# firefly-ice.net
KiCad netlist of a schematic drawn in EAGLE
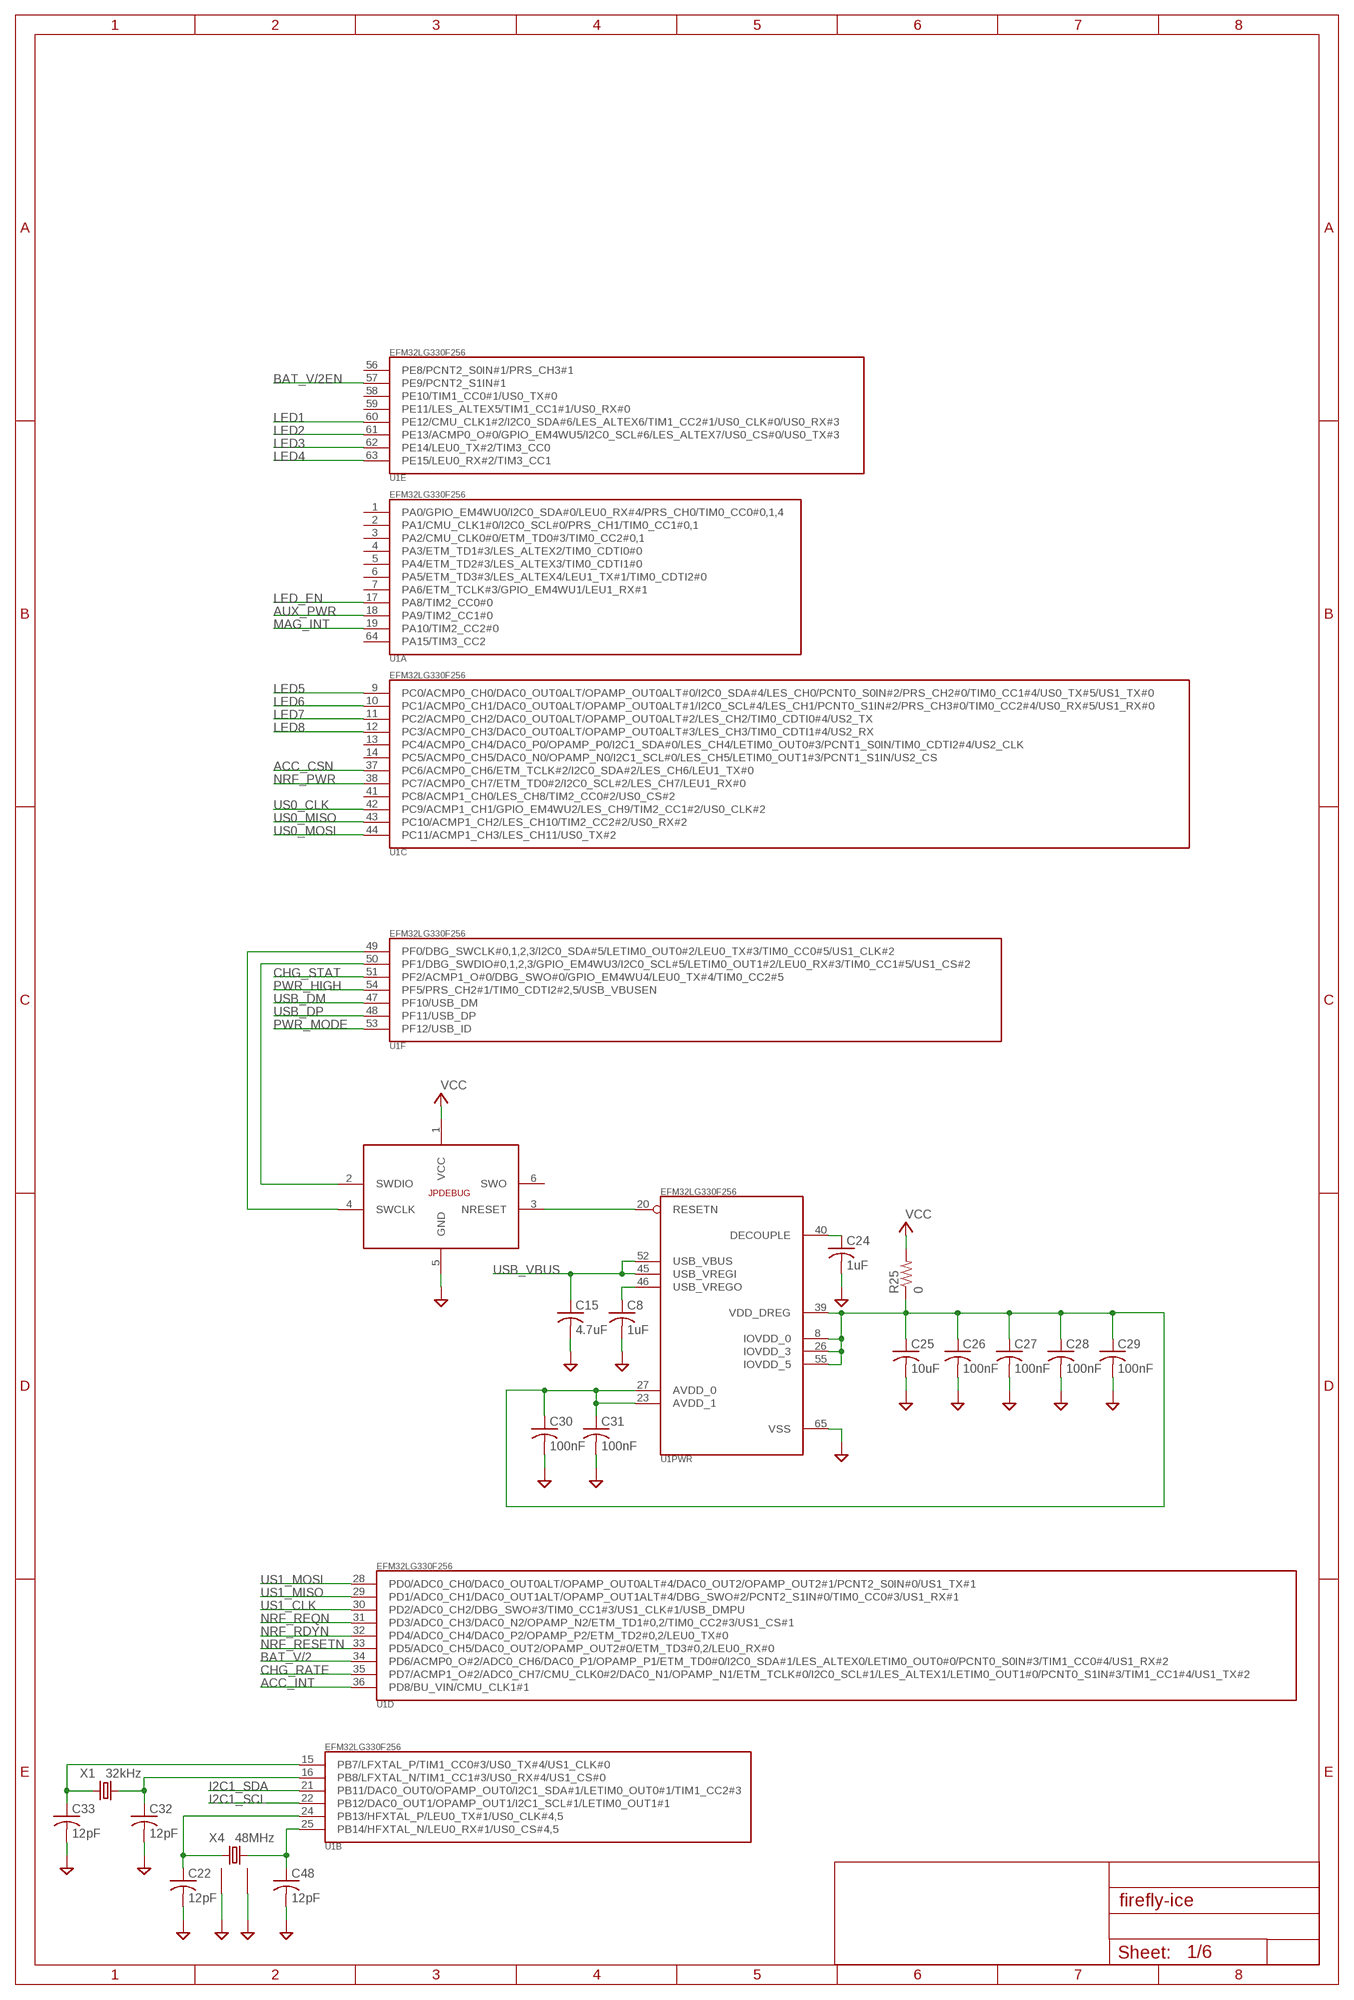
[diagram p0: schematic, sheet 1]
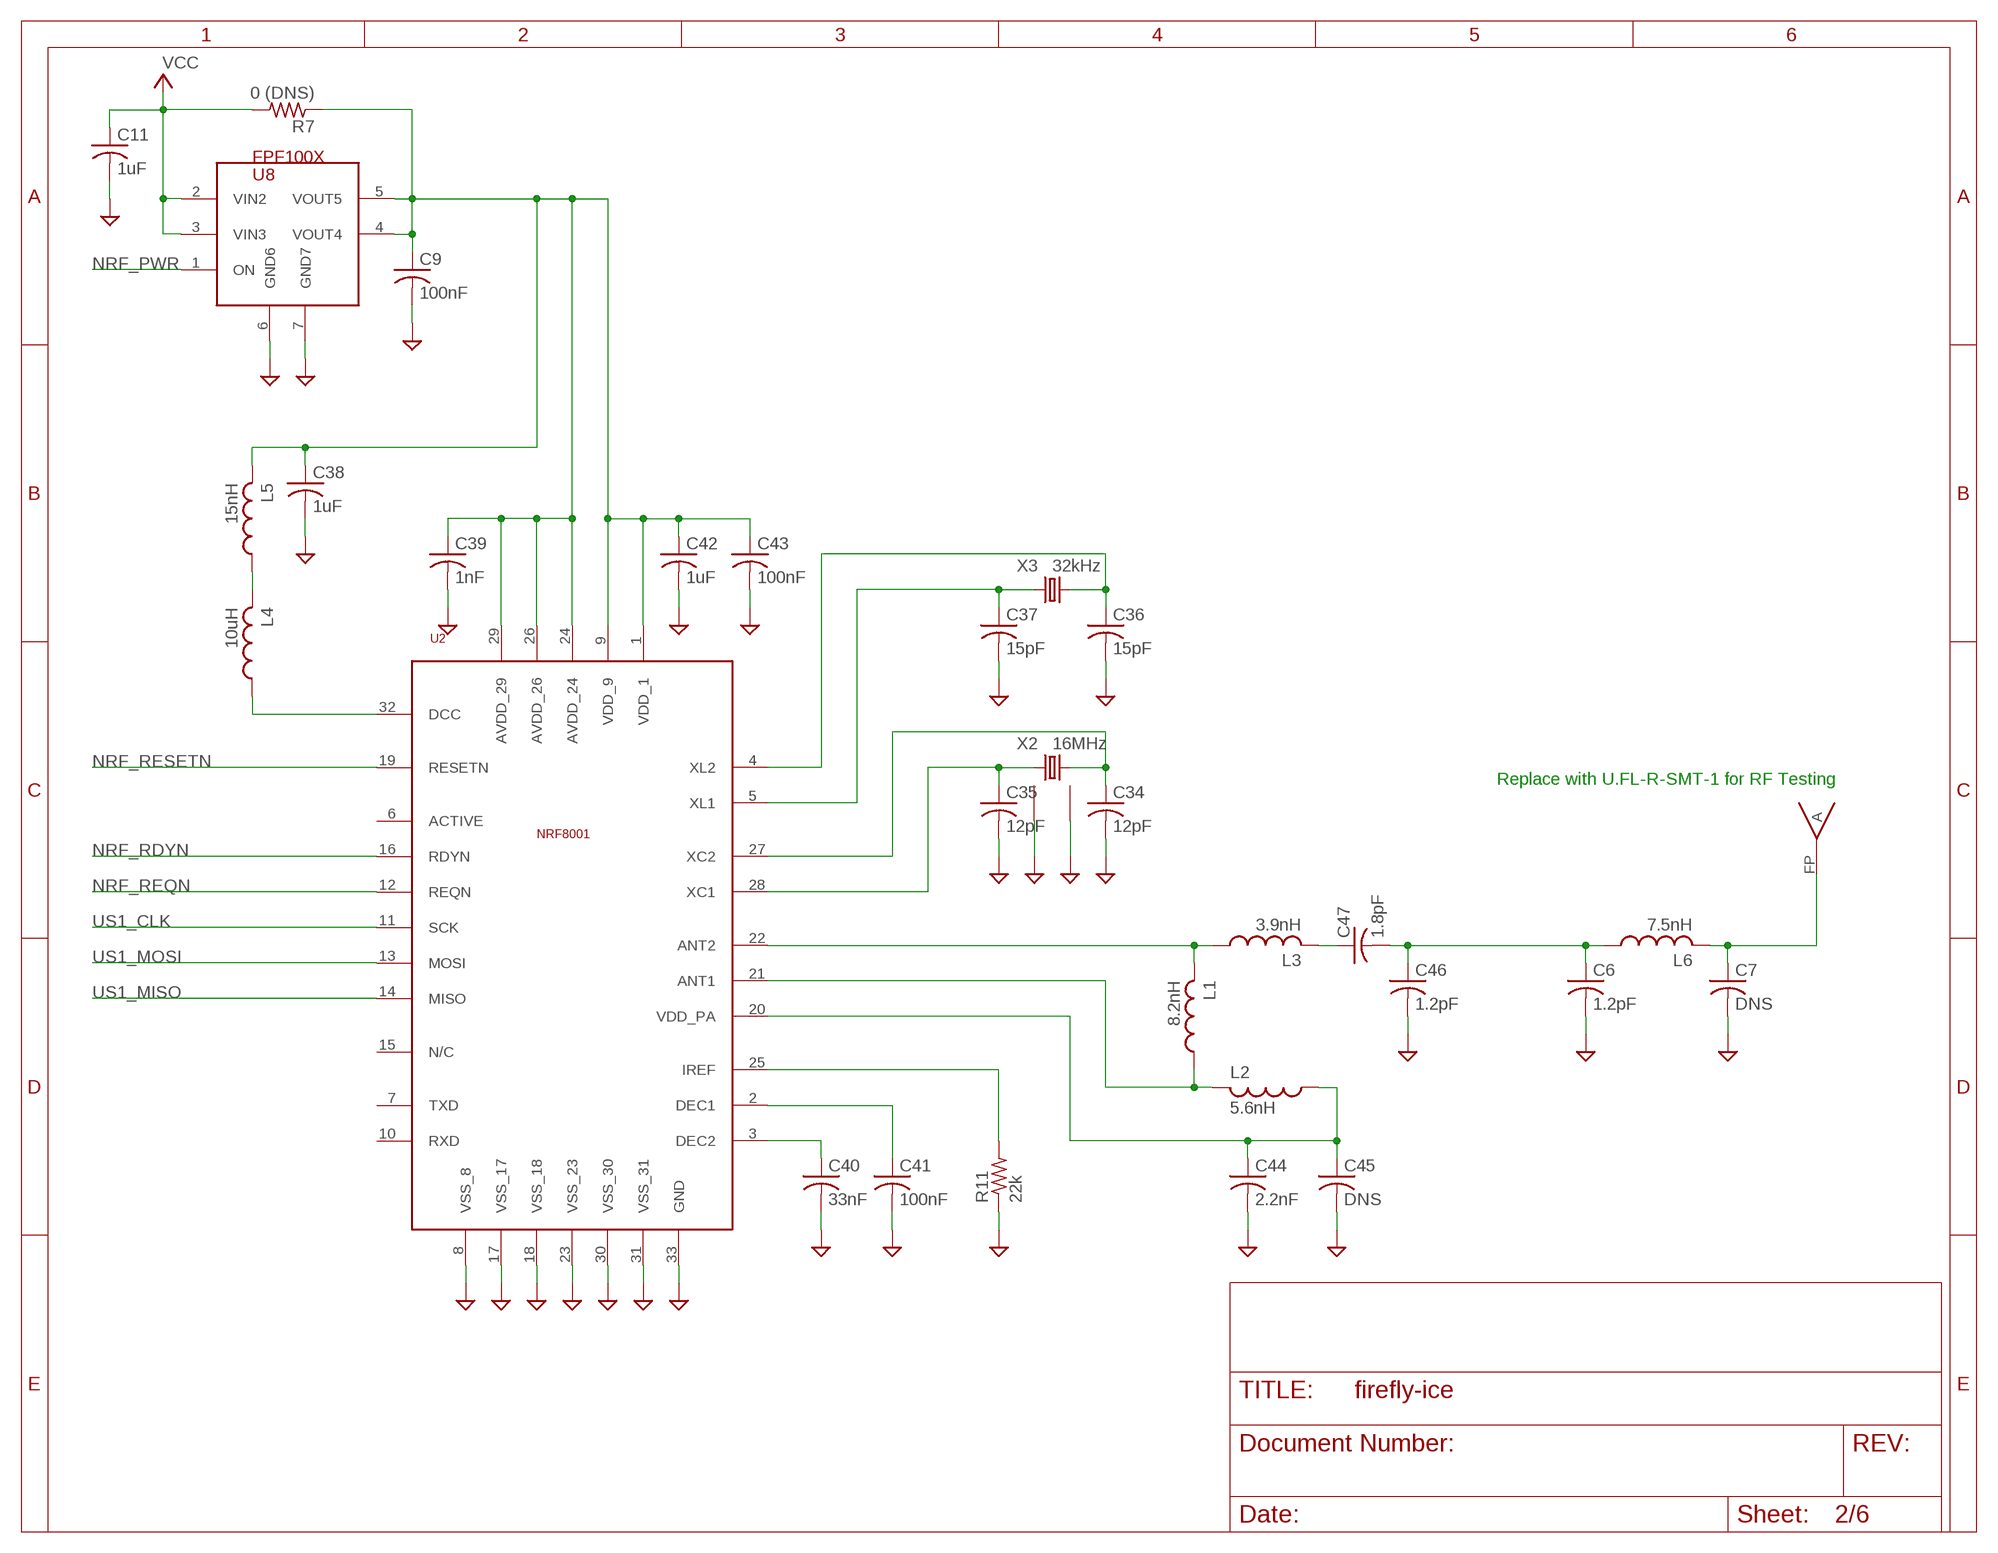
[diagram p1: schematic, sheet 2]
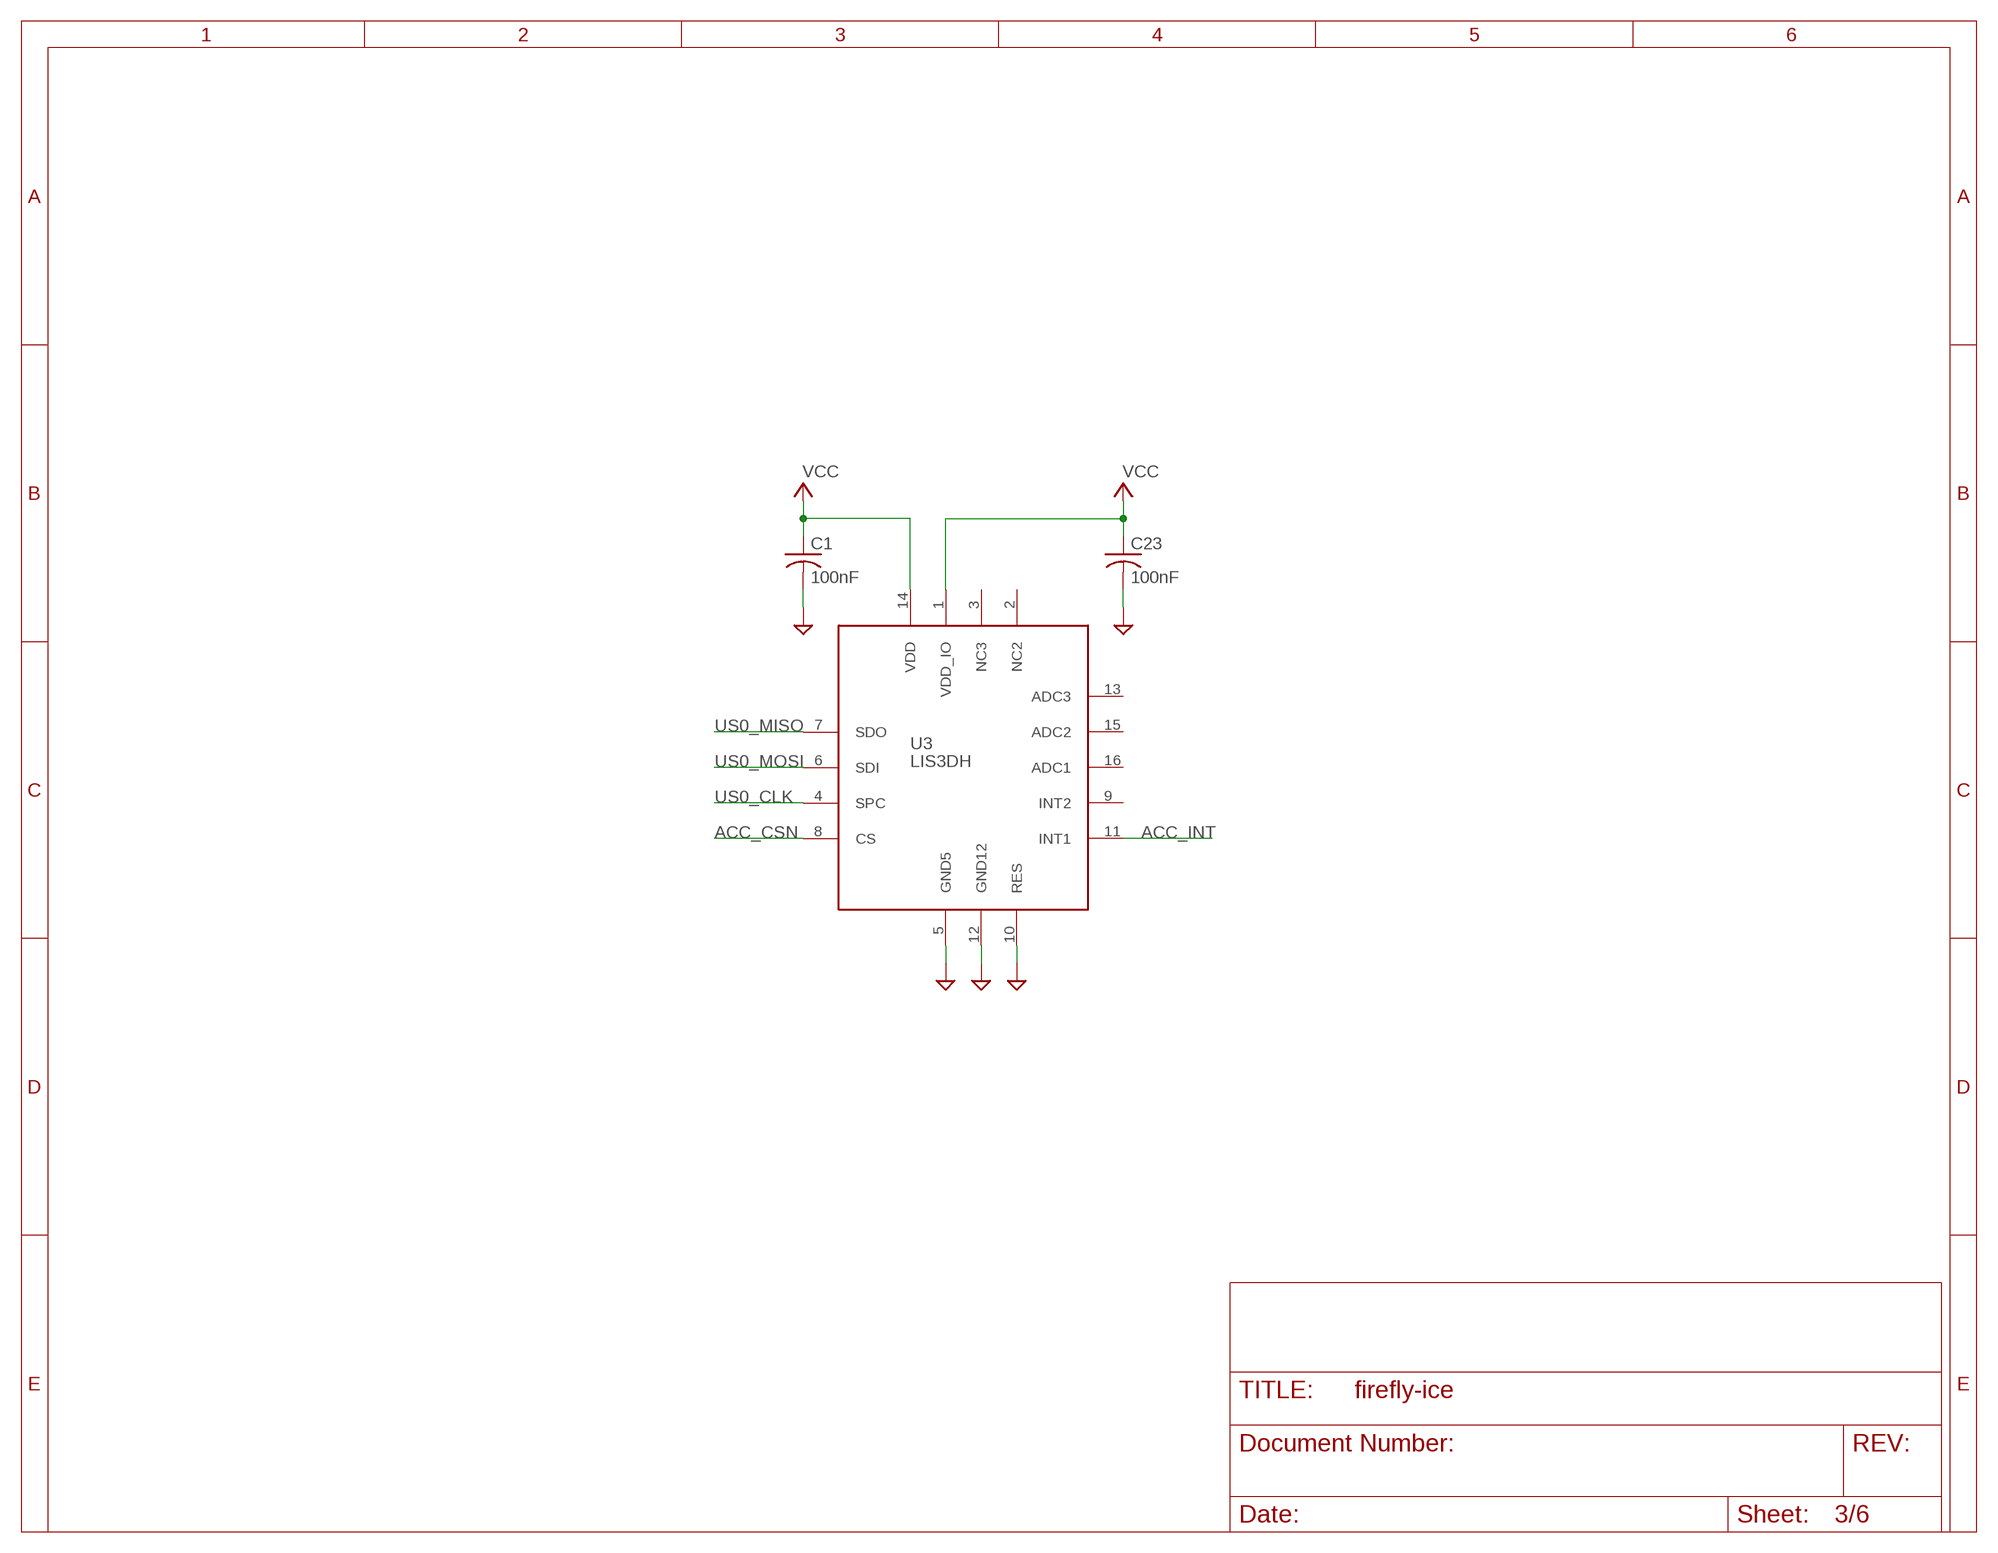
[diagram p2: schematic, sheet 3]
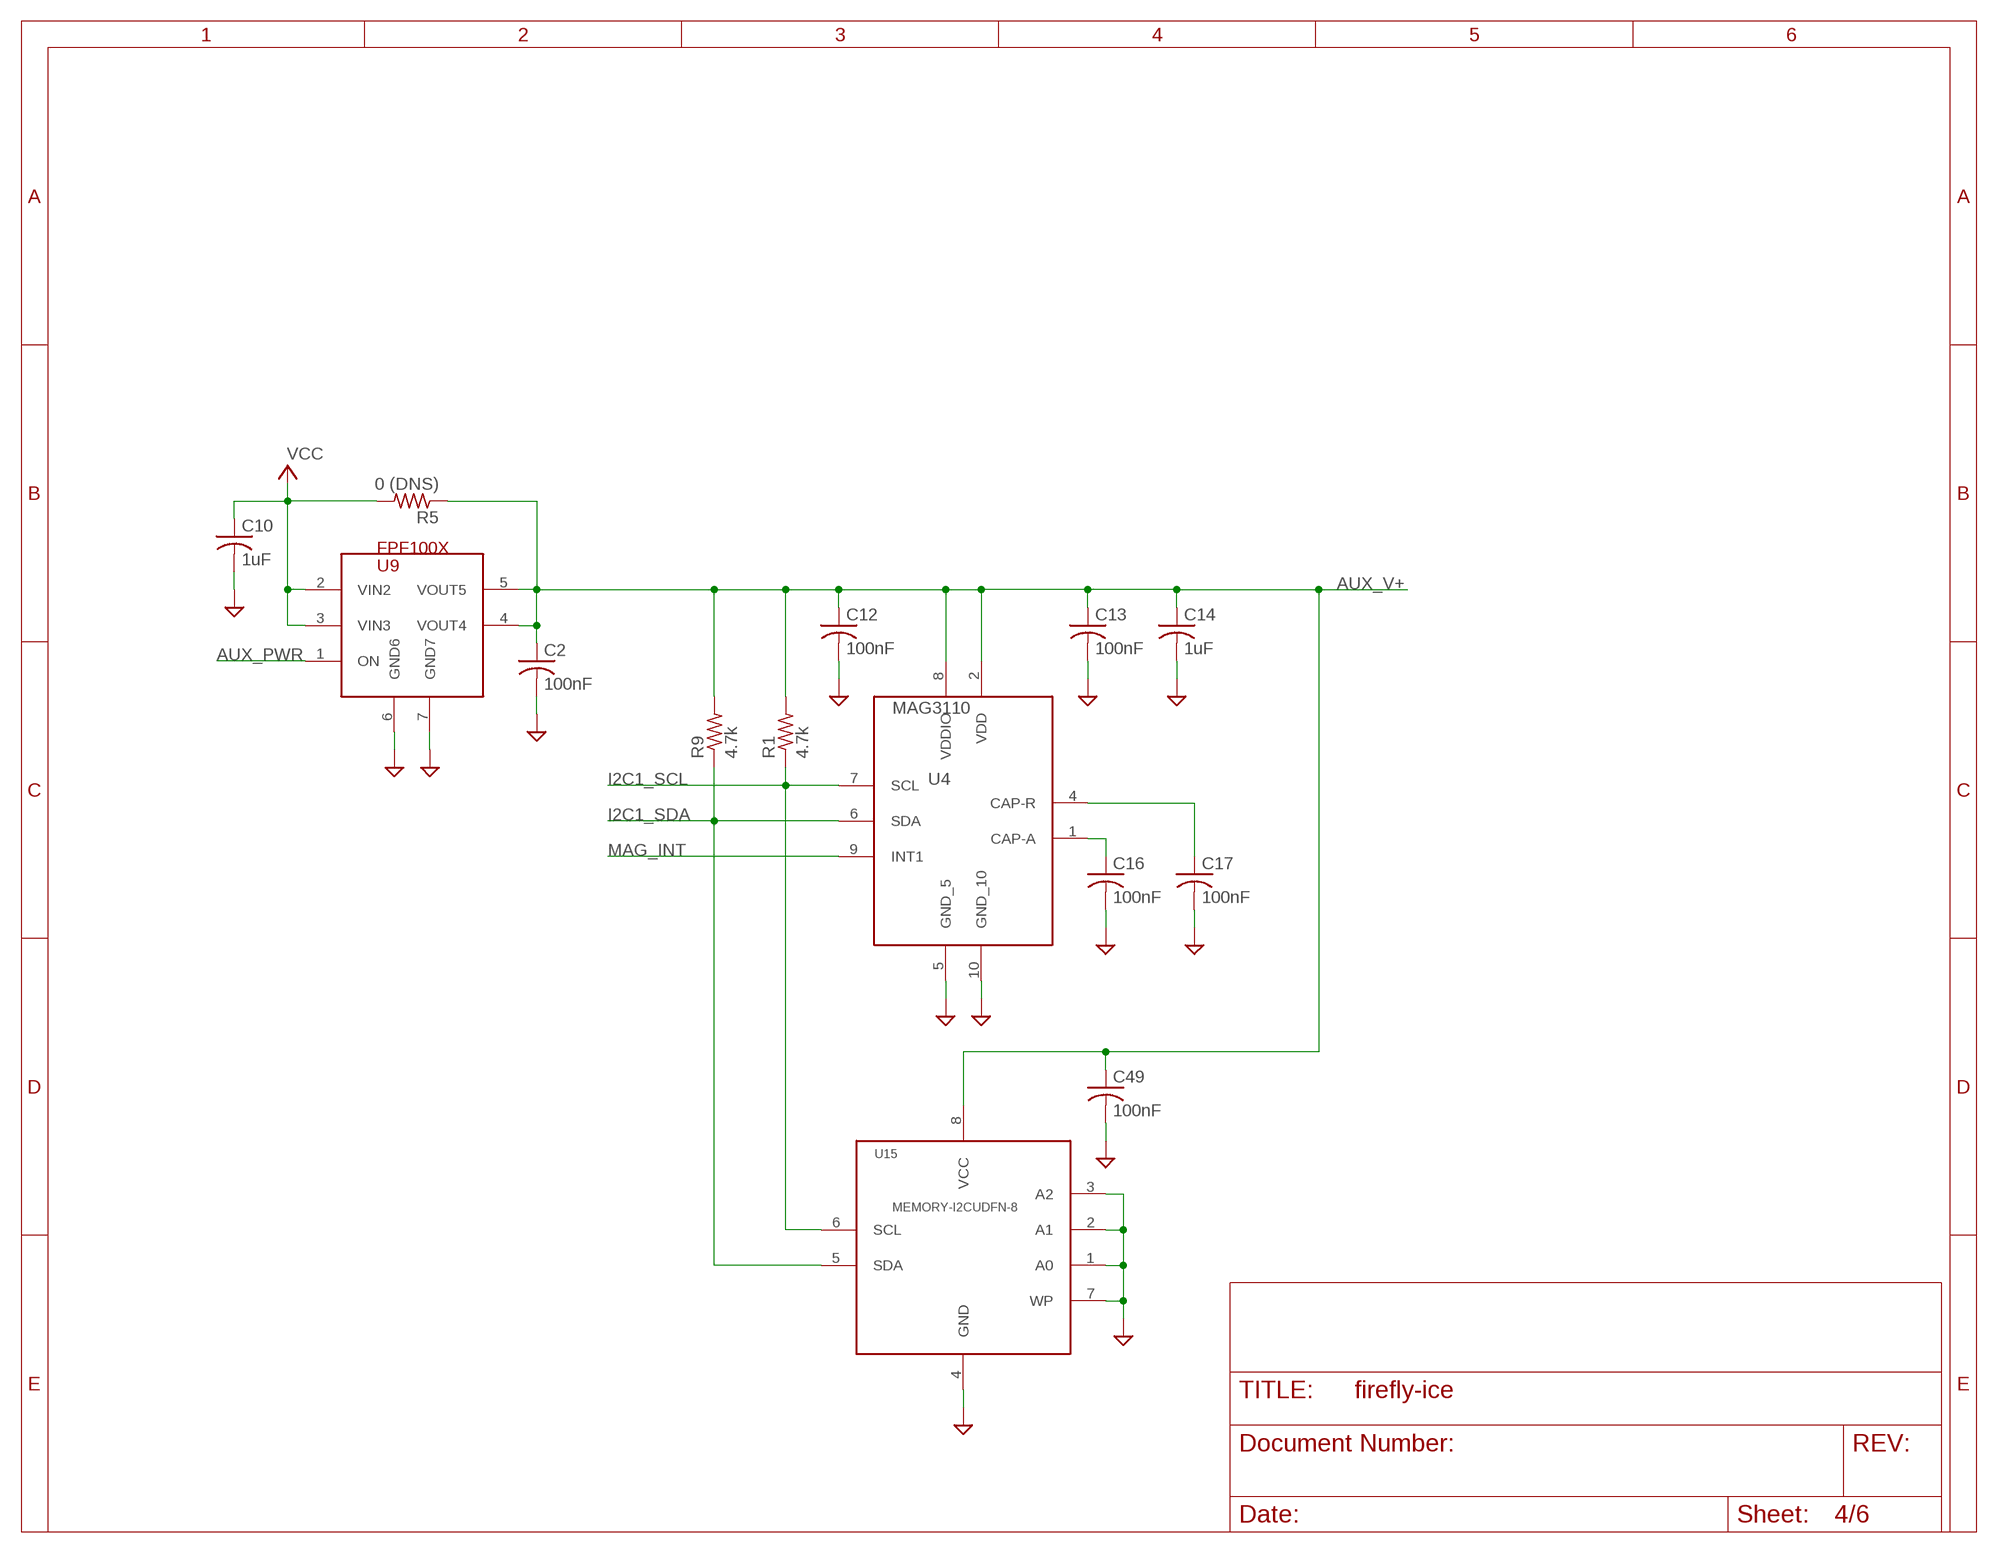
[diagram p3: schematic, sheet 4]
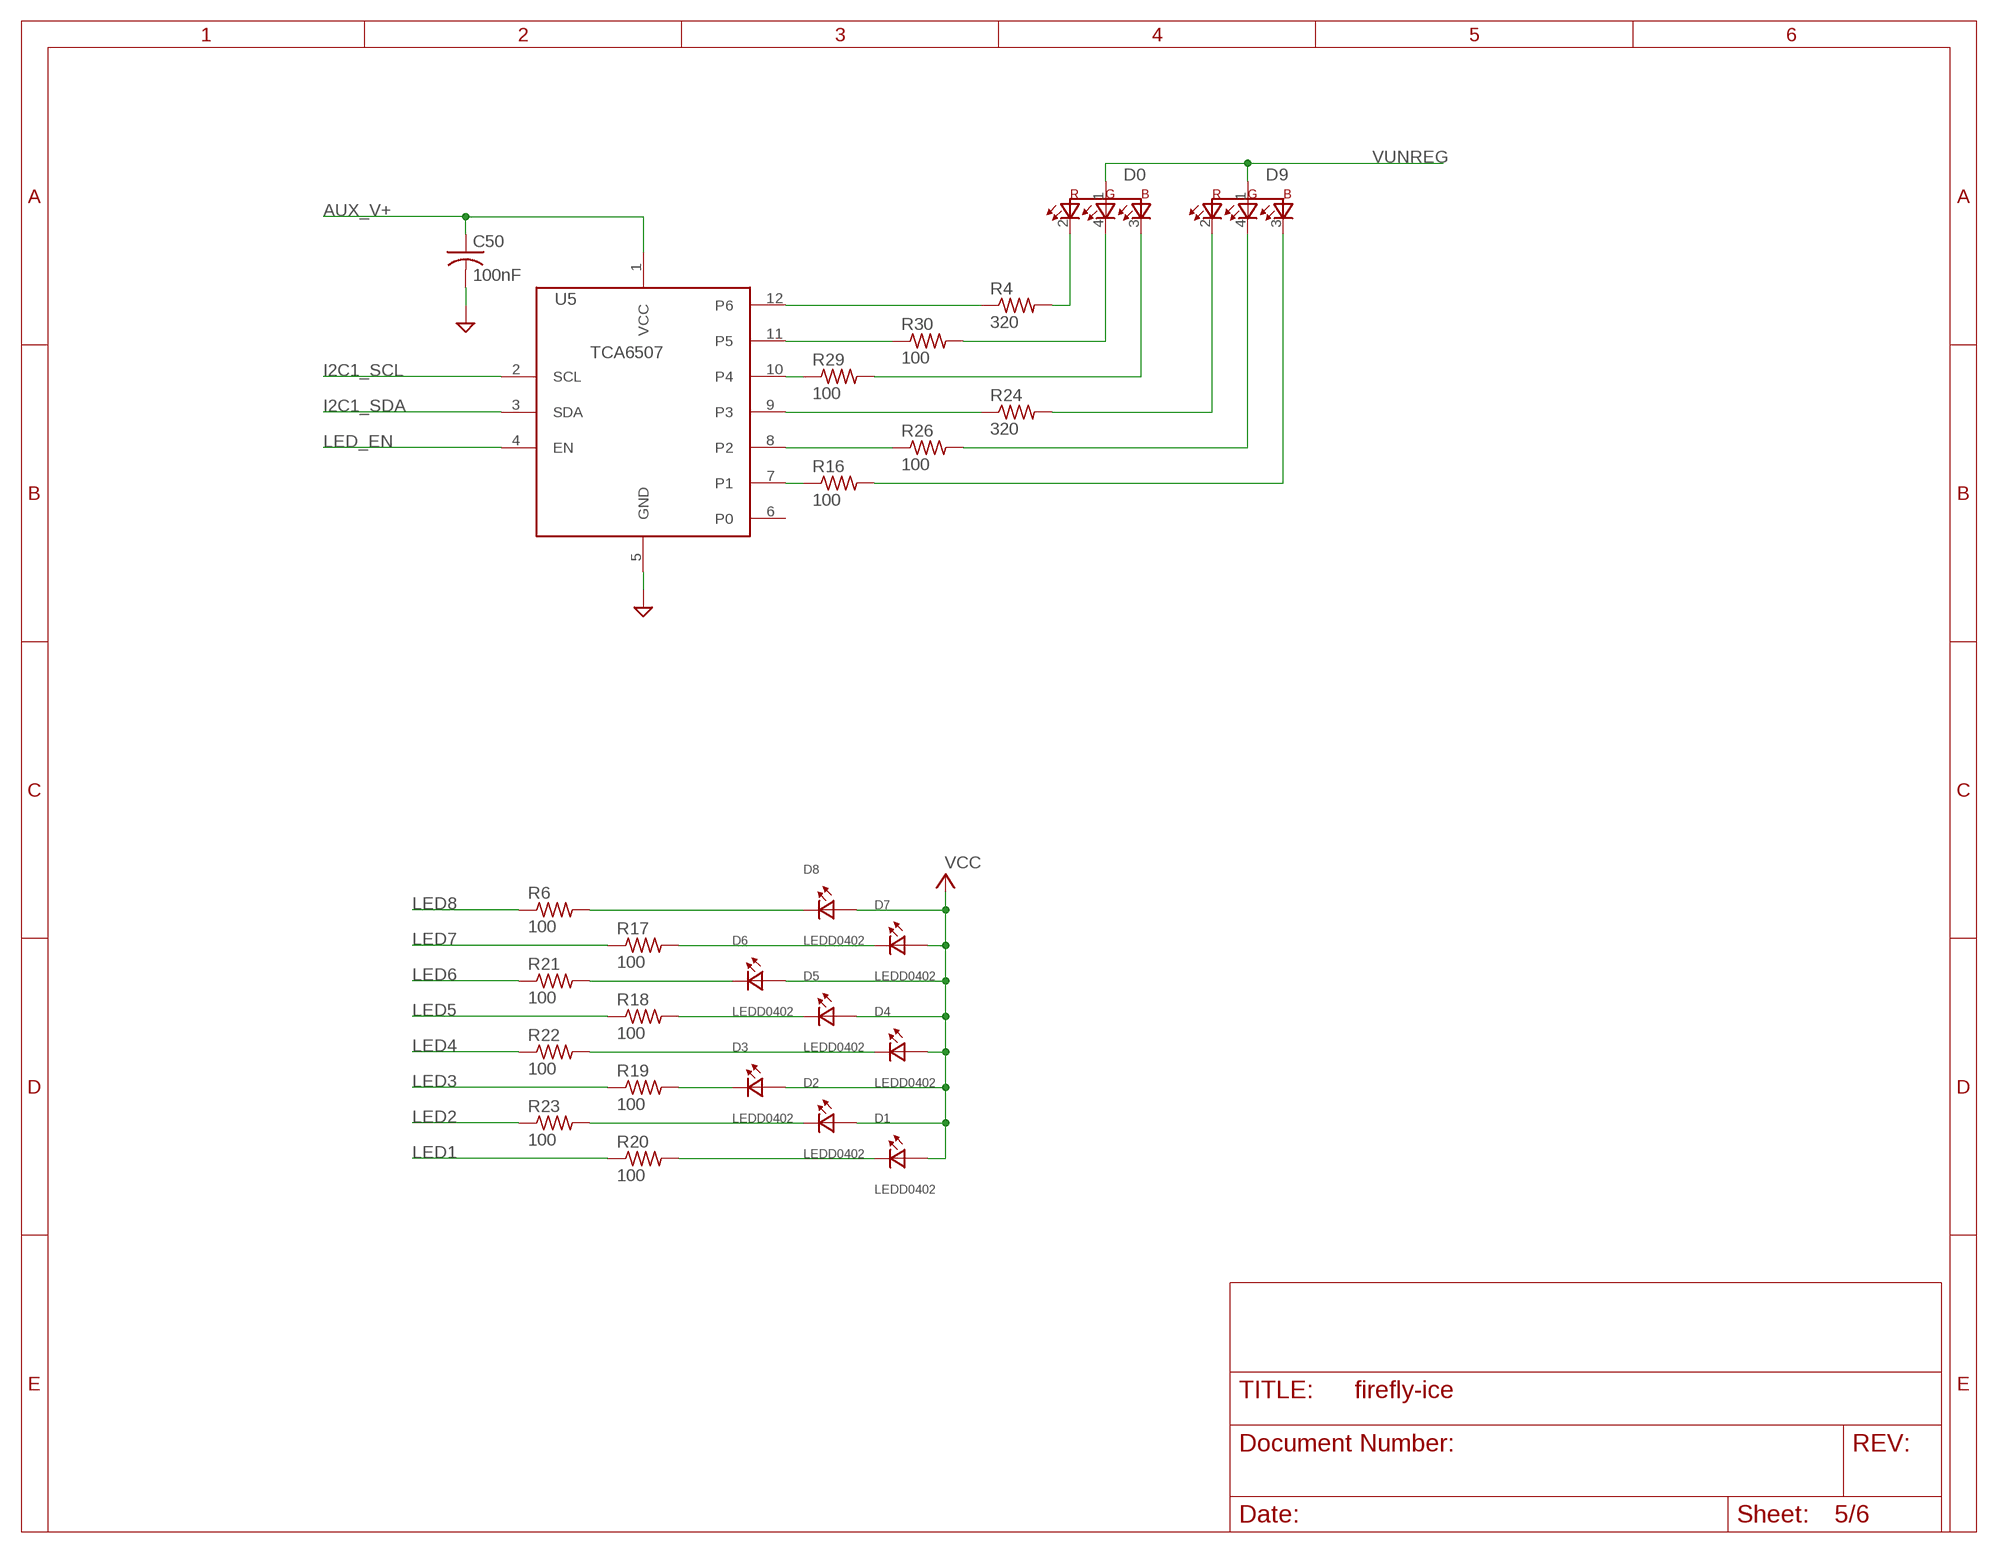
[diagram p4: schematic, sheet 5]
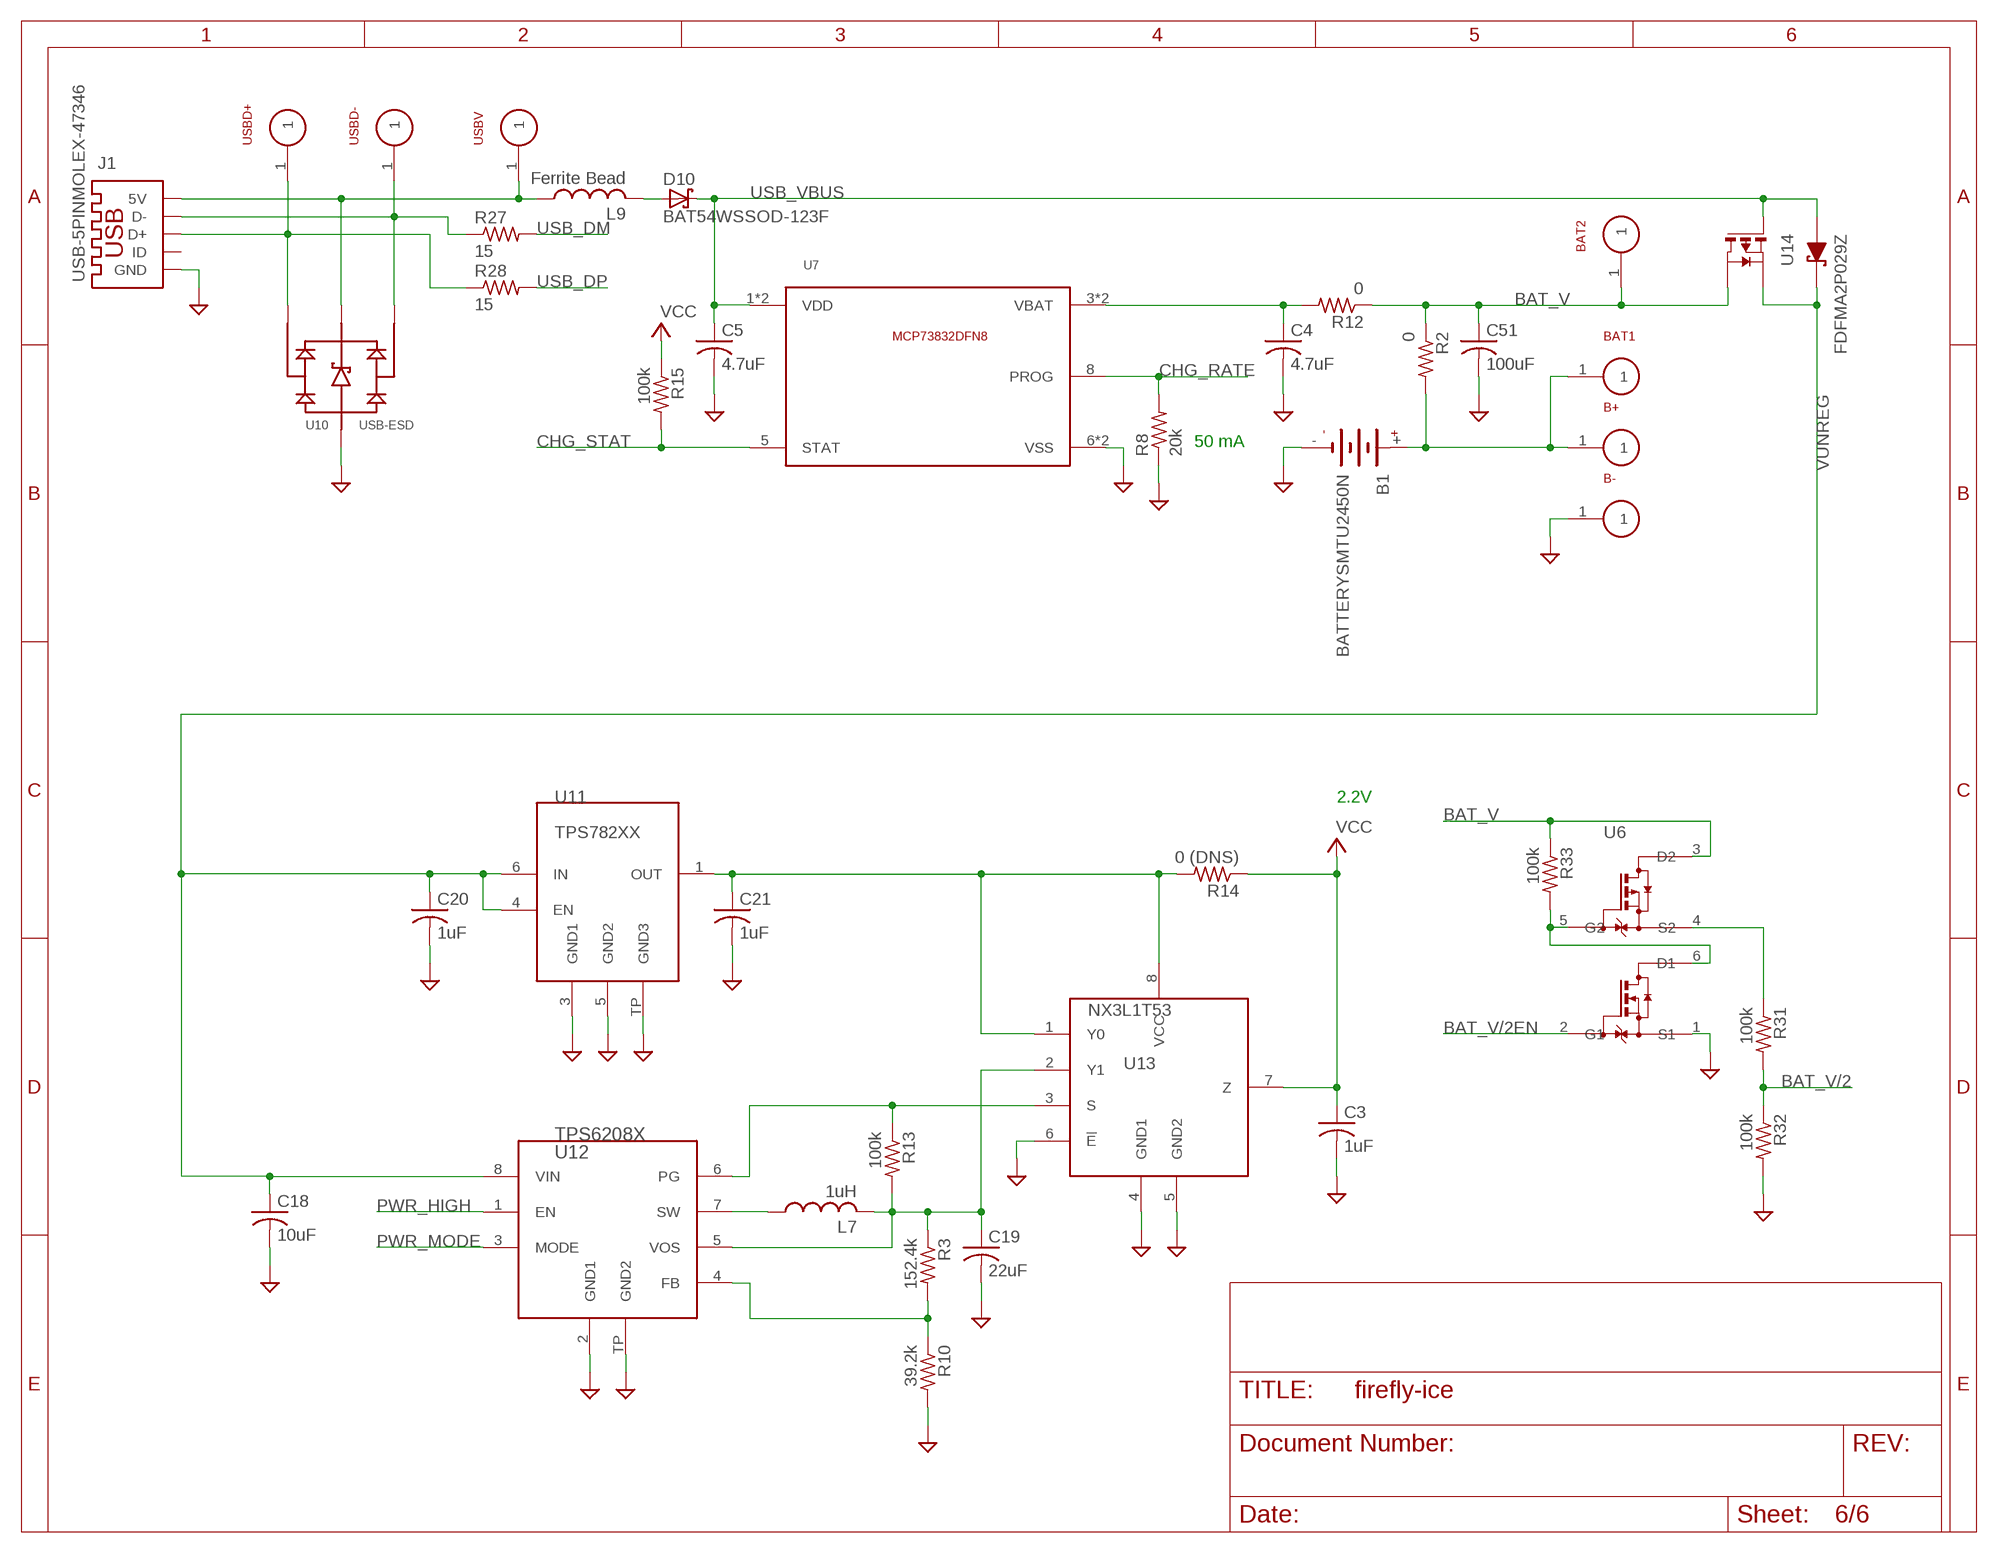
[diagram p5: schematic, sheet 6]

(export (version "E")
  (design (tool "Eeschema 10.0.6"))
  (components
    (comp (ref "B+")
      (value "TARGET-PINWP-28AWG")
      (footprint "eagle-import:WP-28AWG")
      (libsource (lib "eagle-import") (part "TARGET-PINWP-28AWG"))
    )
    (comp (ref "B-")
      (value "TARGET-PINWP-28AWG")
      (footprint "eagle-import:WP-28AWG")
      (libsource (lib "eagle-import") (part "TARGET-PINWP-28AWG"))
    )
    (comp (ref "B1")
      (value "BATTERYSMTU2450N")
      (footprint "eagle-import:SMTU2450N")
      (fields (field (name "MANUFACTURER") "Memory Protection Devices"))
      (libsource (lib "eagle-import") (part "BATTERYSMTU2450N"))
    )
    (comp (ref "BAT1")
      (value "TARGET-PIN")
      (footprint "eagle-import:TARGET-PIN-1MM")
      (libsource (lib "eagle-import") (part "TARGET-PIN"))
    )
    (comp (ref "BAT2")
      (value "TARGET-PIN")
      (footprint "eagle-import:TARGET-PIN-1MM")
      (libsource (lib "eagle-import") (part "TARGET-PIN"))
    )
    (comp (ref "C3")
      (value "1uF")
      (footprint "eagle-import:C0201")
      (fields (field (name "MANUFACTURER") "TDK Corporation"))
      (libsource (lib "eagle-import") (part "C-USC0201"))
    )
    (comp (ref "C4")
      (value "4.7uF")
      (footprint "eagle-import:C0402")
      (fields (field (name "MANUFACTURER") "TDK Corporation"))
      (libsource (lib "eagle-import") (part "C-USC0402"))
    )
    (comp (ref "C5")
      (value "4.7uF")
      (footprint "eagle-import:C0402")
      (fields (field (name "MANUFACTURER") "TDK Corporation"))
      (libsource (lib "eagle-import") (part "C-USC0402"))
    )
    (comp (ref "C18")
      (value "10uF")
      (footprint "eagle-import:C0402")
      (fields (field (name "MANUFACTURER") "TDK Corporation"))
      (libsource (lib "eagle-import") (part "C-USC0402"))
    )
    (comp (ref "C19")
      (value "22uF")
      (footprint "eagle-import:C0603")
      (fields (field (name "MANUFACTURER") "TDK Corporation"))
      (libsource (lib "eagle-import") (part "C-USC0603"))
    )
    (comp (ref "C20")
      (value "1uF")
      (footprint "eagle-import:C0201")
      (fields (field (name "MANUFACTURER") "TDK Corporation"))
      (libsource (lib "eagle-import") (part "C-USC0201"))
    )
    (comp (ref "C21")
      (value "1uF")
      (footprint "eagle-import:C0201")
      (fields (field (name "MANUFACTURER") "TDK Corporation"))
      (libsource (lib "eagle-import") (part "C-USC0201"))
    )
    (comp (ref "C51")
      (value "100uF")
      (footprint "eagle-import:C1206")
      (fields (field (name "MANUFACTURER") "Kemet"))
      (libsource (lib "eagle-import") (part "C-USC1206"))
    )
    (comp (ref "D10")
      (value "BAT54WSSOD-123F")
      (footprint "eagle-import:SOD-123F")
      (fields (field (name "MANUFACTURER") "Rohm Semiconductor"))
      (libsource (lib "eagle-import") (part "BAT54WSSOD-123F"))
    )
    (comp (ref "J1")
      (value "USB-5PINMOLEX-47346")
      (footprint "eagle-import:MOLEX-47346")
      (fields (field (name "MANUFACTURER") "Molex"))
      (libsource (lib "eagle-import") (part "USB-5PINMOLEX-47346"))
    )
    (comp (ref "L7")
      (value "1uH")
      (footprint "eagle-import:L0805")
      (fields (field (name "MANUFACTURER") "WURTH"))
      (libsource (lib "eagle-import") (part "INDUCTORL0805"))
    )
    (comp (ref "L9")
      (value "Ferrite Bead")
      (footprint "eagle-import:L0402")
      (fields (field (name "MANUFACTURER") "Wurth"))
      (libsource (lib "eagle-import") (part "L-USL0402"))
    )
    (comp (ref "R2")
      (value "0")
      (footprint "eagle-import:R0603@1")
      (fields (field (name "MANUFACTURER") "Panasonic Electronic Components"))
      (libsource (lib "eagle-import") (part "R-US_R0603"))
    )
    (comp (ref "R3")
      (value "152.4k")
      (footprint "eagle-import:R0201")
      (fields (field (name "MANUFACTURER") "Panasonic Electronic Components"))
      (libsource (lib "eagle-import") (part "R-US_R0201"))
    )
    (comp (ref "R8")
      (value "20k")
      (footprint "eagle-import:R0201")
      (fields (field (name "MANUFACTURER") "Panasonic Electronic Components"))
      (libsource (lib "eagle-import") (part "R-US_R0201"))
    )
    (comp (ref "R10")
      (value "39.2k")
      (footprint "eagle-import:R0201")
      (fields (field (name "MANUFACTURER") "Panasonic Electronic Components"))
      (libsource (lib "eagle-import") (part "R-US_R0201"))
    )
    (comp (ref "R12")
      (value "0")
      (footprint "eagle-import:R0603@1")
      (fields (field (name "MANUFACTURER") "Panasonic Electronic Components"))
      (libsource (lib "eagle-import") (part "R-US_R0603"))
    )
    (comp (ref "R13")
      (value "100k")
      (footprint "eagle-import:R0201")
      (fields (field (name "MANUFACTURER") "Yageo"))
      (libsource (lib "eagle-import") (part "R-US_R0201"))
    )
    (comp (ref "R14")
      (value "0 (DNS)")
      (footprint "eagle-import:R0201")
      (fields (field (name "MANUFACTURER") "Panasonic Electronic Components"))
      (libsource (lib "eagle-import") (part "R-US_R0201"))
    )
    (comp (ref "R15")
      (value "100k")
      (footprint "eagle-import:R0201")
      (fields (field (name "MANUFACTURER") "Yageo"))
      (libsource (lib "eagle-import") (part "R-US_R0201"))
    )
    (comp (ref "R27")
      (value "15")
      (footprint "eagle-import:R0201")
      (fields (field (name "MANUFACTURER") "Panasonic Electronic Components"))
      (libsource (lib "eagle-import") (part "R-US_R0201"))
    )
    (comp (ref "R28")
      (value "15")
      (footprint "eagle-import:R0201")
      (fields (field (name "MANUFACTURER") "Panasonic Electronic Components"))
      (libsource (lib "eagle-import") (part "R-US_R0201"))
    )
    (comp (ref "R31")
      (value "100k")
      (footprint "eagle-import:R0201")
      (fields (field (name "MANUFACTURER") "Yageo"))
      (libsource (lib "eagle-import") (part "R-US_R0201"))
    )
    (comp (ref "R32")
      (value "100k")
      (footprint "eagle-import:R0201")
      (fields (field (name "MANUFACTURER") "Yageo"))
      (libsource (lib "eagle-import") (part "R-US_R0201"))
    )
    (comp (ref "R33")
      (value "100k")
      (footprint "eagle-import:R0201")
      (fields (field (name "MANUFACTURER") "Yageo"))
      (libsource (lib "eagle-import") (part "R-US_R0201"))
    )
    (comp (ref "U6")
      (value "MOSFET-N+PSOT963")
      (footprint "eagle-import:SOT963")
      (fields (field (name "MANUFACTURER") "Diodes Inc"))
      (libsource (lib "eagle-import") (part "MOSFET-N+PSOT963"))
    )
    (comp (ref "U7")
      (value "MCP73832DFN8")
      (footprint "eagle-import:DFN8")
      (fields (field (name "MANUFACTURER") "Microchip"))
      (libsource (lib "eagle-import") (part "MCP73832DFN8"))
    )
    (comp (ref "U10")
      (value "USB-ESD")
      (footprint "eagle-import:UQFN6")
      (fields (field (name "MANUFACTURER") "STMicroelectronics"))
      (libsource (lib "eagle-import") (part "USB-ESD"))
    )
    (comp (ref "U11")
      (value "TPS782XX")
      (footprint "eagle-import:S-PWSON-N6")
      (fields (field (name "MANUFACTURER") "Texas Instruments"))
      (libsource (lib "eagle-import") (part "TPS782XX"))
    )
    (comp (ref "U12")
      (value "TPS6208X")
      (footprint "eagle-import:S-PWSON-N8")
      (fields (field (name "MANUFACTURER") "Texas Instruments"))
      (libsource (lib "eagle-import") (part "TPS6208X"))
    )
    (comp (ref "U13")
      (value "NX3L1T53")
      (footprint "eagle-import:SOT902-2")
      (fields (field (name "MANUFACTURER") "NXP Semiconductor"))
      (libsource (lib "eagle-import") (part "NX3L1T53"))
    )
    (comp (ref "U14")
      (value "FDFMA2P029Z")
      (footprint "eagle-import:MO-229")
      (fields (field (name "MANUFACTURER") "Fairchild Semiconductor"))
      (libsource (lib "eagle-import") (part "FDFMA2P029Z"))
    )
    (comp (ref "USBD+")
      (value "TARGET-PIN")
      (footprint "eagle-import:TARGET-PIN-1MM")
      (libsource (lib "eagle-import") (part "TARGET-PIN"))
    )
    (comp (ref "USBD-")
      (value "TARGET-PIN")
      (footprint "eagle-import:TARGET-PIN-1MM")
      (libsource (lib "eagle-import") (part "TARGET-PIN"))
    )
    (comp (ref "USBV")
      (value "TARGET-PIN")
      (footprint "eagle-import:TARGET-PIN-1MM")
      (libsource (lib "eagle-import") (part "TARGET-PIN"))
    )
    (comp (ref "C50")
      (value "100nF")
      (footprint "eagle-import:C0201")
      (fields (field (name "MANUFACTURER") "Murata"))
      (libsource (lib "eagle-import") (part "C-USC0201"))
    )
    (comp (ref "D0")
      (value "LED-RGB-CASMLP34")
      (footprint "eagle-import:SMLP34")
      (fields (field (name "MANUFACTURER") "ROHM Semiconductor"))
      (libsource (lib "eagle-import") (part "LED-RGB-CASMLP34"))
    )
    (comp (ref "D1")
      (value "LEDD0402")
      (footprint "eagle-import:D0402")
      (fields (field (name "MANUFACTURER") "Rohm Semiconductor"))
      (libsource (lib "eagle-import") (part "LEDD0402"))
    )
    (comp (ref "D2")
      (value "LEDD0402")
      (footprint "eagle-import:D0402")
      (fields (field (name "MANUFACTURER") "Rohm Semiconductor"))
      (libsource (lib "eagle-import") (part "LEDD0402"))
    )
    (comp (ref "D3")
      (value "LEDD0402")
      (footprint "eagle-import:D0402")
      (fields (field (name "MANUFACTURER") "Rohm Semiconductor"))
      (libsource (lib "eagle-import") (part "LEDD0402"))
    )
    (comp (ref "D4")
      (value "LEDD0402")
      (footprint "eagle-import:D0402")
      (fields (field (name "MANUFACTURER") "Rohm Semiconductor"))
      (libsource (lib "eagle-import") (part "LEDD0402"))
    )
    (comp (ref "D5")
      (value "LEDD0402")
      (footprint "eagle-import:D0402")
      (fields (field (name "MANUFACTURER") "Rohm Semiconductor"))
      (libsource (lib "eagle-import") (part "LEDD0402"))
    )
    (comp (ref "D6")
      (value "LEDD0402")
      (footprint "eagle-import:D0402")
      (fields (field (name "MANUFACTURER") "Rohm Semiconductor"))
      (libsource (lib "eagle-import") (part "LEDD0402"))
    )
    (comp (ref "D7")
      (value "LEDD0402")
      (footprint "eagle-import:D0402")
      (fields (field (name "MANUFACTURER") "Rohm Semiconductor"))
      (libsource (lib "eagle-import") (part "LEDD0402"))
    )
    (comp (ref "D8")
      (value "LEDD0402")
      (footprint "eagle-import:D0402")
      (fields (field (name "MANUFACTURER") "Rohm Semiconductor"))
      (libsource (lib "eagle-import") (part "LEDD0402"))
    )
    (comp (ref "D9")
      (value "LED-RGB-CASMLP34")
      (footprint "eagle-import:SMLP34")
      (fields (field (name "MANUFACTURER") "ROHM Semiconductor"))
      (libsource (lib "eagle-import") (part "LED-RGB-CASMLP34"))
    )
    (comp (ref "R4")
      (value "320")
      (footprint "eagle-import:R0201")
      (fields (field (name "MANUFACTURER") "Panasonic Electronic Components"))
      (libsource (lib "eagle-import") (part "R-US_R0201"))
    )
    (comp (ref "R6")
      (value "100")
      (footprint "eagle-import:R0201")
      (fields (field (name "MANUFACTURER") "Panasonic Electronic Components"))
      (libsource (lib "eagle-import") (part "R-US_R0201"))
    )
    (comp (ref "R16")
      (value "100")
      (footprint "eagle-import:R0201")
      (fields (field (name "MANUFACTURER") "Panasonic Electronic Components"))
      (libsource (lib "eagle-import") (part "R-US_R0201"))
    )
    (comp (ref "R17")
      (value "100")
      (footprint "eagle-import:R0201")
      (fields (field (name "MANUFACTURER") "Panasonic Electronic Components"))
      (libsource (lib "eagle-import") (part "R-US_R0201"))
    )
    (comp (ref "R18")
      (value "100")
      (footprint "eagle-import:R0201")
      (fields (field (name "MANUFACTURER") "Panasonic Electronic Components"))
      (libsource (lib "eagle-import") (part "R-US_R0201"))
    )
    (comp (ref "R19")
      (value "100")
      (footprint "eagle-import:R0201")
      (fields (field (name "MANUFACTURER") "Panasonic Electronic Components"))
      (libsource (lib "eagle-import") (part "R-US_R0201"))
    )
    (comp (ref "R20")
      (value "100")
      (footprint "eagle-import:R0201")
      (fields (field (name "MANUFACTURER") "Panasonic Electronic Components"))
      (libsource (lib "eagle-import") (part "R-US_R0201"))
    )
    (comp (ref "R21")
      (value "100")
      (footprint "eagle-import:R0201")
      (fields (field (name "MANUFACTURER") "Panasonic Electronic Components"))
      (libsource (lib "eagle-import") (part "R-US_R0201"))
    )
    (comp (ref "R22")
      (value "100")
      (footprint "eagle-import:R0201")
      (fields (field (name "MANUFACTURER") "Panasonic Electronic Components"))
      (libsource (lib "eagle-import") (part "R-US_R0201"))
    )
    (comp (ref "R23")
      (value "100")
      (footprint "eagle-import:R0201")
      (fields (field (name "MANUFACTURER") "Panasonic Electronic Components"))
      (libsource (lib "eagle-import") (part "R-US_R0201"))
    )
    (comp (ref "R24")
      (value "320")
      (footprint "eagle-import:R0201")
      (fields (field (name "MANUFACTURER") "Panasonic Electronic Components"))
      (libsource (lib "eagle-import") (part "R-US_R0201"))
    )
    (comp (ref "R26")
      (value "100")
      (footprint "eagle-import:R0201")
      (fields (field (name "MANUFACTURER") "Panasonic Electronic Components"))
      (libsource (lib "eagle-import") (part "R-US_R0201"))
    )
    (comp (ref "R29")
      (value "100")
      (footprint "eagle-import:R0201")
      (fields (field (name "MANUFACTURER") "Panasonic Electronic Components"))
      (libsource (lib "eagle-import") (part "R-US_R0201"))
    )
    (comp (ref "R30")
      (value "100")
      (footprint "eagle-import:R0201")
      (fields (field (name "MANUFACTURER") "Panasonic Electronic Components"))
      (libsource (lib "eagle-import") (part "R-US_R0201"))
    )
    (comp (ref "U5")
      (value "TCA6507")
      (footprint "eagle-import:R-PX2QFN-N12")
      (fields (field (name "MANUFACTURER") "ROHM Semiconductor"))
      (libsource (lib "eagle-import") (part "TCA6507"))
    )
    (comp (ref "C8")
      (value "1uF")
      (footprint "eagle-import:C0201")
      (fields (field (name "MANUFACTURER") "TDK Corporation"))
      (libsource (lib "eagle-import") (part "C-USC0201"))
    )
    (comp (ref "C15")
      (value "4.7uF")
      (footprint "eagle-import:C0402")
      (fields (field (name "MANUFACTURER") "TDK Corporation"))
      (libsource (lib "eagle-import") (part "C-USC0402"))
    )
    (comp (ref "C22")
      (value "12pF")
      (footprint "eagle-import:C0201")
      (fields (field (name "MANUFACTURER") "Kemet"))
      (libsource (lib "eagle-import") (part "C-USC0201"))
    )
    (comp (ref "C24")
      (value "1uF")
      (footprint "eagle-import:C0201")
      (fields (field (name "MANUFACTURER") "TDK Corporation"))
      (libsource (lib "eagle-import") (part "C-USC0201"))
    )
    (comp (ref "C25")
      (value "10uF")
      (footprint "eagle-import:C0402")
      (fields (field (name "MANUFACTURER") "TDK Corporation"))
      (libsource (lib "eagle-import") (part "C-USC0402"))
    )
    (comp (ref "C26")
      (value "100nF")
      (footprint "eagle-import:C0201")
      (fields (field (name "MANUFACTURER") "Murata"))
      (libsource (lib "eagle-import") (part "C-USC0201"))
    )
    (comp (ref "C27")
      (value "100nF")
      (footprint "eagle-import:C0201")
      (fields (field (name "MANUFACTURER") "Murata"))
      (libsource (lib "eagle-import") (part "C-USC0201"))
    )
    (comp (ref "C28")
      (value "100nF")
      (footprint "eagle-import:C0201")
      (fields (field (name "MANUFACTURER") "Murata"))
      (libsource (lib "eagle-import") (part "C-USC0201"))
    )
    (comp (ref "C29")
      (value "100nF")
      (footprint "eagle-import:C0201")
      (fields (field (name "MANUFACTURER") "Murata"))
      (libsource (lib "eagle-import") (part "C-USC0201"))
    )
    (comp (ref "C30")
      (value "100nF")
      (footprint "eagle-import:C0201")
      (fields (field (name "MANUFACTURER") "Murata"))
      (libsource (lib "eagle-import") (part "C-USC0201"))
    )
    (comp (ref "C31")
      (value "100nF")
      (footprint "eagle-import:C0201")
      (fields (field (name "MANUFACTURER") "Murata"))
      (libsource (lib "eagle-import") (part "C-USC0201"))
    )
    (comp (ref "C32")
      (value "12pF")
      (footprint "eagle-import:C0201")
      (fields (field (name "MANUFACTURER") "Kemet"))
      (libsource (lib "eagle-import") (part "C-USC0201"))
    )
    (comp (ref "C33")
      (value "12pF")
      (footprint "eagle-import:C0201")
      (fields (field (name "MANUFACTURER") "Kemet"))
      (libsource (lib "eagle-import") (part "C-USC0201"))
    )
    (comp (ref "C48")
      (value "12pF")
      (footprint "eagle-import:C0201")
      (fields (field (name "MANUFACTURER") "Kemet"))
      (libsource (lib "eagle-import") (part "C-USC0201"))
    )
    (comp (ref "JPDEBUG")
      (value "TC2030-SWD")
      (footprint "eagle-import:TC2030-MCP-NL")
      (libsource (lib "eagle-import") (part "TC2030-SWD"))
    )
    (comp (ref "R25")
      (value "0")
      (footprint "eagle-import:R0603@1")
      (fields (field (name "MANUFACTURER") "Panasonic Electronic Components"))
      (libsource (lib "eagle-import") (part "R-US_R0603"))
    )
    (comp (ref "U1")
      (value "EFM32LG330F256")
      (footprint "eagle-import:QFN64")
      (fields (field (name "MANUFACTURER") "Energy Micro") (field (name "ORDERING-CODE") "EFM32LG330F256"))
      (libsource (lib "eagle-import") (part "EFM32LG330F256"))
    )
    (comp (ref "X1")
      (value "32kHz")
      (footprint "eagle-import:9HT10")
      (fields (field (name "MANUFACTURER") "TXC CORPORATION"))
      (libsource (lib "eagle-import") (part "XTAL29HT10"))
    )
    (comp (ref "X4")
      (value "48MHz")
      (footprint "eagle-import:ABM11")
      (fields (field (name "MANUFACTURER") "Abracon Corporation"))
      (libsource (lib "eagle-import") (part "XTALABM11"))
    )
    (comp (ref "C1")
      (value "100nF")
      (footprint "eagle-import:C0201")
      (fields (field (name "MANUFACTURER") "Murata"))
      (libsource (lib "eagle-import") (part "C-USC0201"))
    )
    (comp (ref "C23")
      (value "100nF")
      (footprint "eagle-import:C0201")
      (fields (field (name "MANUFACTURER") "Murata"))
      (libsource (lib "eagle-import") (part "C-USC0201"))
    )
    (comp (ref "U3")
      (value "LIS3DH")
      (footprint "eagle-import:LGA16_3X3")
      (fields (field (name "MANUFACTURER") "ST"))
      (libsource (lib "eagle-import") (part "LIS3DH"))
    )
    (comp (ref "A1")
      (value "FR05_S1_N_0_110")
      (footprint "eagle-import:FR05_S1_N_0_110")
      (fields (field (name "MANUFACTURER") "Fractus"))
      (libsource (lib "eagle-import") (part "FR05_S1_N_0_110"))
    )
    (comp (ref "C6")
      (value "1.2pF")
      (footprint "eagle-import:C0201")
      (fields (field (name "MANUFACTURER") "TDK"))
      (libsource (lib "eagle-import") (part "C-USC0201"))
    )
    (comp (ref "C7")
      (value "DNS")
      (footprint "eagle-import:C0201")
      (libsource (lib "eagle-import") (part "C-USC0201"))
    )
    (comp (ref "C9")
      (value "100nF")
      (footprint "eagle-import:C0201")
      (fields (field (name "MANUFACTURER") "Murata"))
      (libsource (lib "eagle-import") (part "C-USC0201"))
    )
    (comp (ref "C11")
      (value "1uF")
      (footprint "eagle-import:C0201")
      (fields (field (name "MANUFACTURER") "TDK Corporation"))
      (libsource (lib "eagle-import") (part "C-USC0201"))
    )
    (comp (ref "C34")
      (value "12pF")
      (footprint "eagle-import:C0201")
      (fields (field (name "MANUFACTURER") "Kemet"))
      (libsource (lib "eagle-import") (part "C-USC0201"))
    )
    (comp (ref "C35")
      (value "12pF")
      (footprint "eagle-import:C0201")
      (fields (field (name "MANUFACTURER") "Kemet"))
      (libsource (lib "eagle-import") (part "C-USC0201"))
    )
    (comp (ref "C36")
      (value "15pF")
      (footprint "eagle-import:C0201")
      (fields (field (name "MANUFACTURER") "Kemet"))
      (libsource (lib "eagle-import") (part "C-USC0201"))
    )
    (comp (ref "C37")
      (value "15pF")
      (footprint "eagle-import:C0201")
      (fields (field (name "MANUFACTURER") "Kemet"))
      (libsource (lib "eagle-import") (part "C-USC0201"))
    )
    (comp (ref "C38")
      (value "1uF")
      (footprint "eagle-import:C0201")
      (fields (field (name "MANUFACTURER") "TDK Corporation"))
      (libsource (lib "eagle-import") (part "C-USC0201"))
    )
    (comp (ref "C39")
      (value "1nF")
      (footprint "eagle-import:C0201")
      (fields (field (name "MANUFACTURER") "Murata"))
      (libsource (lib "eagle-import") (part "C-USC0201"))
    )
    (comp (ref "C40")
      (value "33nF")
      (footprint "eagle-import:C0201")
      (fields (field (name "MANUFACTURER") "Murata"))
      (libsource (lib "eagle-import") (part "C-USC0201"))
    )
    (comp (ref "C41")
      (value "100nF")
      (footprint "eagle-import:C0201")
      (fields (field (name "MANUFACTURER") "Kemet"))
      (libsource (lib "eagle-import") (part "C-USC0201"))
    )
    (comp (ref "C42")
      (value "1uF")
      (footprint "eagle-import:C0201")
      (fields (field (name "MANUFACTURER") "TDK Corporation"))
      (libsource (lib "eagle-import") (part "C-USC0201"))
    )
    (comp (ref "C43")
      (value "100nF")
      (footprint "eagle-import:C0201")
      (fields (field (name "MANUFACTURER") "Murata"))
      (libsource (lib "eagle-import") (part "C-USC0201"))
    )
    (comp (ref "C44")
      (value "2.2nF")
      (footprint "eagle-import:C0201")
      (fields (field (name "MANUFACTURER") "TDK"))
      (libsource (lib "eagle-import") (part "C-USC0201"))
    )
    (comp (ref "C45")
      (value "DNS")
      (footprint "eagle-import:C0201")
      (libsource (lib "eagle-import") (part "C-USC0201"))
    )
    (comp (ref "C46")
      (value "1.2pF")
      (footprint "eagle-import:C0201")
      (fields (field (name "MANUFACTURER") "TDK"))
      (libsource (lib "eagle-import") (part "C-USC0201"))
    )
    (comp (ref "C47")
      (value "1.8pF")
      (footprint "eagle-import:C0201")
      (fields (field (name "MANUFACTURER") "TDK"))
      (libsource (lib "eagle-import") (part "C-USC0201"))
    )
    (comp (ref "L1")
      (value "8.2nH")
      (footprint "eagle-import:L0201")
      (fields (field (name "MANUFACTURER") "TDK"))
      (libsource (lib "eagle-import") (part "L-USL0201"))
    )
    (comp (ref "L2")
      (value "5.6nH")
      (footprint "eagle-import:L0201")
      (fields (field (name "MANUFACTURER") "TDK"))
      (libsource (lib "eagle-import") (part "L-USL0201"))
    )
    (comp (ref "L3")
      (value "3.9nH")
      (footprint "eagle-import:L0201")
      (fields (field (name "MANUFACTURER") "TDK"))
      (libsource (lib "eagle-import") (part "L-USL0201"))
    )
    (comp (ref "L4")
      (value "10uH")
      (footprint "eagle-import:0603")
      (fields (field (name "MANUFACTURER") "TDK"))
      (libsource (lib "eagle-import") (part "INDUCTOR0603"))
    )
    (comp (ref "L5")
      (value "15nH")
      (footprint "eagle-import:L0201")
      (fields (field (name "MANUFACTURER") "TDK"))
      (libsource (lib "eagle-import") (part "L-USL0201"))
    )
    (comp (ref "L6")
      (value "7.5nH")
      (footprint "eagle-import:L0201")
      (fields (field (name "MANUFACTURER") "Taiyo Yuden"))
      (libsource (lib "eagle-import") (part "L-USL0201"))
    )
    (comp (ref "R7")
      (value "0 (DNS)")
      (footprint "eagle-import:R0201")
      (fields (field (name "MANUFACTURER") "Panasonic Electronic Components"))
      (libsource (lib "eagle-import") (part "R-US_R0201"))
    )
    (comp (ref "R11")
      (value "22k")
      (footprint "eagle-import:R0201")
      (fields (field (name "MANUFACTURER") "Panasonic"))
      (libsource (lib "eagle-import") (part "R-US_R0201"))
    )
    (comp (ref "U2")
      (value "NRF8001")
      (footprint "eagle-import:QFN-32")
      (fields (field (name "MANUFACTURER") "Nordic Semiconductor"))
      (libsource (lib "eagle-import") (part "NRF8001"))
    )
    (comp (ref "U8")
      (value "FPF100X")
      (footprint "eagle-import:MICROFET-2X2-6L")
      (fields (field (name "MANUFACTURER") "Fairchild Semiconductor"))
      (libsource (lib "eagle-import") (part "FPF100X"))
    )
    (comp (ref "X2")
      (value "16MHz")
      (footprint "eagle-import:TSX-3225")
      (fields (field (name "MANUFACTURER") "TXC CORPORATION"))
      (libsource (lib "eagle-import") (part "XTALTSX-3225"))
    )
    (comp (ref "X3")
      (value "32kHz")
      (footprint "eagle-import:9HT10")
      (fields (field (name "MANUFACTURER") "TXC CORPORATION"))
      (libsource (lib "eagle-import") (part "XTAL29HT10"))
    )
    (comp (ref "C2")
      (value "100nF")
      (footprint "eagle-import:C0201")
      (fields (field (name "MANUFACTURER") "Murata"))
      (libsource (lib "eagle-import") (part "C-USC0201"))
    )
    (comp (ref "C10")
      (value "1uF")
      (footprint "eagle-import:C0201")
      (fields (field (name "MANUFACTURER") "TDK Corporation"))
      (libsource (lib "eagle-import") (part "C-USC0201"))
    )
    (comp (ref "C12")
      (value "100nF")
      (footprint "eagle-import:C0201")
      (fields (field (name "MANUFACTURER") "Murata"))
      (libsource (lib "eagle-import") (part "C-USC0201"))
    )
    (comp (ref "C13")
      (value "100nF")
      (footprint "eagle-import:C0201")
      (fields (field (name "MANUFACTURER") "Murata"))
      (libsource (lib "eagle-import") (part "C-USC0201"))
    )
    (comp (ref "C14")
      (value "1uF")
      (footprint "eagle-import:C0201")
      (fields (field (name "MANUFACTURER") "TDK Corporation"))
      (libsource (lib "eagle-import") (part "C-USC0201"))
    )
    (comp (ref "C16")
      (value "100nF")
      (footprint "eagle-import:C0201")
      (fields (field (name "MANUFACTURER") "Murata"))
      (libsource (lib "eagle-import") (part "C-USC0201"))
    )
    (comp (ref "C17")
      (value "100nF")
      (footprint "eagle-import:C0201")
      (fields (field (name "MANUFACTURER") "Murata"))
      (libsource (lib "eagle-import") (part "C-USC0201"))
    )
    (comp (ref "C49")
      (value "100nF")
      (footprint "eagle-import:C0201")
      (fields (field (name "MANUFACTURER") "Murata"))
      (libsource (lib "eagle-import") (part "C-USC0201"))
    )
    (comp (ref "R1")
      (value "4.7k")
      (footprint "eagle-import:R0201")
      (fields (field (name "MANUFACTURER") "Panasonic Electronic Components"))
      (libsource (lib "eagle-import") (part "R-US_R0201"))
    )
    (comp (ref "R5")
      (value "0 (DNS)")
      (footprint "eagle-import:R0201")
      (fields (field (name "MANUFACTURER") "Panasonic Electronic Components"))
      (libsource (lib "eagle-import") (part "R-US_R0201"))
    )
    (comp (ref "R9")
      (value "4.7k")
      (footprint "eagle-import:R0201")
      (fields (field (name "MANUFACTURER") "Panasonic Electronic Components"))
      (libsource (lib "eagle-import") (part "R-US_R0201"))
    )
    (comp (ref "U4")
      (value "MAG3110")
      (footprint "eagle-import:DFN10-2X2")
      (fields (field (name "MANUFACTURER") "Freescale Semiconductor"))
      (libsource (lib "eagle-import") (part "MAG3110"))
    )
    (comp (ref "U9")
      (value "FPF100X")
      (footprint "eagle-import:MICROFET-2X2-6L")
      (fields (field (name "MANUFACTURER") "Fairchild Semiconductor"))
      (libsource (lib "eagle-import") (part "FPF100X"))
    )
    (comp (ref "U15")
      (value "MEMORY-I2CUDFN-8")
      (footprint "eagle-import:UDFN-8")
      (fields (field (name "MANUFACTURER") "Atmel"))
      (libsource (lib "eagle-import") (part "MEMORY-I2CUDFN-8"))
    )
  )
  (nets
    (net (code "1") (name "ACC_CSN") (class "Default")
      (node (ref "U1") (pin "37") (pinfunction "PC6/ACMP0_CH6/ETM_TCLK#2/I2C0_SDA#2/LES_CH6/LEU1_TX#0_37") (pintype "bidirectional"))
      (node (ref "U3") (pin "8") (pinfunction "CS_8") (pintype "bidirectional"))
    )
    (net (code "2") (name "ACC_INT") (class "Default")
      (node (ref "U1") (pin "36") (pinfunction "PD8/BU_VIN/CMU_CLK1#1_36") (pintype "bidirectional"))
      (node (ref "U3") (pin "11") (pinfunction "INT1_11") (pintype "bidirectional"))
    )
    (net (code "3") (name "AUX_PWR") (class "Default")
      (node (ref "U1") (pin "18") (pinfunction "PA9/TIM2_CC1#0_18") (pintype "bidirectional"))
      (node (ref "U9") (pin "1") (pinfunction "ON_1") (pintype "bidirectional"))
    )
    (net (code "4") (name "AUX_V+") (class "Default")
      (node (ref "C12") (pin "1") (pinfunction "1_1") (pintype "passive"))
      (node (ref "C13") (pin "1") (pinfunction "1_1") (pintype "passive"))
      (node (ref "C14") (pin "1") (pinfunction "1_1") (pintype "passive"))
      (node (ref "C2") (pin "1") (pinfunction "1_1") (pintype "passive"))
      (node (ref "C49") (pin "1") (pinfunction "1_1") (pintype "passive"))
      (node (ref "C50") (pin "1") (pinfunction "1_1") (pintype "passive"))
      (node (ref "R1") (pin "2") (pinfunction "2_2") (pintype "passive"))
      (node (ref "R5") (pin "1") (pinfunction "1_1") (pintype "passive"))
      (node (ref "R9") (pin "2") (pinfunction "2_2") (pintype "passive"))
      (node (ref "U15") (pin "8") (pinfunction "VCC_8") (pintype "bidirectional"))
      (node (ref "U4") (pin "2") (pinfunction "VDD_2") (pintype "bidirectional"))
      (node (ref "U4") (pin "8") (pinfunction "VDDIO_8") (pintype "bidirectional"))
      (node (ref "U5") (pin "1") (pinfunction "VCC_1") (pintype "bidirectional"))
      (node (ref "U9") (pin "4") (pinfunction "VOUT4_4") (pintype "bidirectional"))
      (node (ref "U9") (pin "5") (pinfunction "VOUT5_5") (pintype "bidirectional"))
    )
    (net (code "5") (name "BAT_V") (class "Default")
      (node (ref "BAT2") (pin "1") (pinfunction "1_1") (pintype "bidirectional"))
      (node (ref "C51") (pin "1") (pinfunction "1_1") (pintype "passive"))
      (node (ref "R12") (pin "1") (pinfunction "1_1") (pintype "passive"))
      (node (ref "R2") (pin "1") (pinfunction "1_1") (pintype "passive"))
      (node (ref "R33") (pin "1") (pinfunction "1_1") (pintype "passive"))
      (node (ref "U14") (pin "4") (pinfunction "S_4") (pintype "passive"))
      (node (ref "U6") (pin "3") (pinfunction "D2_3") (pintype "passive"))
    )
    (net (code "6") (name "BAT_V{slash}2") (class "Default")
      (node (ref "R31") (pin "2") (pinfunction "2_2") (pintype "passive"))
      (node (ref "R32") (pin "1") (pinfunction "1_1") (pintype "passive"))
      (node (ref "U1") (pin "34") (pinfunction "PD6/ACMP0_O#2/ADC0_CH6/DAC0_P1/OPAMP_P1/ETM_TD0#0/I2C0_SDA#1/LES_ALTEX0/LETIM0_OUT0#0/PCNT0_S0IN#3/TIM1_CC0#4/US1_RX#2_34") (pintype "bidirectional"))
    )
    (net (code "7") (name "BAT_V{slash}2EN") (class "Default")
      (node (ref "U1") (pin "57") (pinfunction "PE9/PCNT2_S1IN#1_57") (pintype "bidirectional"))
      (node (ref "U6") (pin "2") (pinfunction "G1_2") (pintype "passive"))
    )
    (net (code "8") (name "CHG_RATE") (class "Default")
      (node (ref "R8") (pin "2") (pinfunction "2_2") (pintype "passive"))
      (node (ref "U1") (pin "35") (pinfunction "PD7/ACMP1_O#2/ADC0_CH7/CMU_CLK0#2/DAC0_N1/OPAMP_N1/ETM_TCLK#0/I2C0_SCL#1/LES_ALTEX1/LETIM0_OUT1#0/PCNT0_S1IN#3/TIM1_CC1#4/US1_TX#2_35") (pintype "bidirectional"))
      (node (ref "U7") (pin "8") (pinfunction "PROG_8") (pintype "bidirectional"))
    )
    (net (code "9") (name "CHG_STAT") (class "Default")
      (node (ref "R15") (pin "2") (pinfunction "2_2") (pintype "passive"))
      (node (ref "U1") (pin "51") (pinfunction "PF2/ACMP1_O#0/DBG_SWO#0/GPIO_EM4WU4/LEU0_TX#4/TIM0_CC2#5_51") (pintype "bidirectional"))
      (node (ref "U7") (pin "5") (pinfunction "STAT_5") (pintype "bidirectional"))
    )
    (net (code "10") (name "GND") (class "Default")
      (node (ref "B-") (pin "1") (pinfunction "1_1") (pintype "bidirectional"))
      (node (ref "B1") (pin "-") (pinfunction "-_-") (pintype "passive"))
      (node (ref "C1") (pin "2") (pinfunction "2_2") (pintype "passive"))
      (node (ref "C10") (pin "2") (pinfunction "2_2") (pintype "passive"))
      (node (ref "C11") (pin "2") (pinfunction "2_2") (pintype "passive"))
      (node (ref "C12") (pin "2") (pinfunction "2_2") (pintype "passive"))
      (node (ref "C13") (pin "2") (pinfunction "2_2") (pintype "passive"))
      (node (ref "C14") (pin "2") (pinfunction "2_2") (pintype "passive"))
      (node (ref "C15") (pin "2") (pinfunction "2_2") (pintype "passive"))
      (node (ref "C16") (pin "2") (pinfunction "2_2") (pintype "passive"))
      (node (ref "C17") (pin "2") (pinfunction "2_2") (pintype "passive"))
      (node (ref "C18") (pin "2") (pinfunction "2_2") (pintype "passive"))
      (node (ref "C19") (pin "2") (pinfunction "2_2") (pintype "passive"))
      (node (ref "C2") (pin "2") (pinfunction "2_2") (pintype "passive"))
      (node (ref "C20") (pin "2") (pinfunction "2_2") (pintype "passive"))
      (node (ref "C21") (pin "2") (pinfunction "2_2") (pintype "passive"))
      (node (ref "C22") (pin "2") (pinfunction "2_2") (pintype "passive"))
      (node (ref "C23") (pin "2") (pinfunction "2_2") (pintype "passive"))
      (node (ref "C24") (pin "2") (pinfunction "2_2") (pintype "passive"))
      (node (ref "C25") (pin "2") (pinfunction "2_2") (pintype "passive"))
      (node (ref "C26") (pin "2") (pinfunction "2_2") (pintype "passive"))
      (node (ref "C27") (pin "2") (pinfunction "2_2") (pintype "passive"))
      (node (ref "C28") (pin "2") (pinfunction "2_2") (pintype "passive"))
      (node (ref "C29") (pin "2") (pinfunction "2_2") (pintype "passive"))
      (node (ref "C3") (pin "2") (pinfunction "2_2") (pintype "passive"))
      (node (ref "C30") (pin "2") (pinfunction "2_2") (pintype "passive"))
      (node (ref "C31") (pin "2") (pinfunction "2_2") (pintype "passive"))
      (node (ref "C32") (pin "2") (pinfunction "2_2") (pintype "passive"))
      (node (ref "C33") (pin "2") (pinfunction "2_2") (pintype "passive"))
      (node (ref "C34") (pin "2") (pinfunction "2_2") (pintype "passive"))
      (node (ref "C35") (pin "2") (pinfunction "2_2") (pintype "passive"))
      (node (ref "C36") (pin "2") (pinfunction "2_2") (pintype "passive"))
      (node (ref "C37") (pin "2") (pinfunction "2_2") (pintype "passive"))
      (node (ref "C38") (pin "2") (pinfunction "2_2") (pintype "passive"))
      (node (ref "C39") (pin "2") (pinfunction "2_2") (pintype "passive"))
      (node (ref "C4") (pin "2") (pinfunction "2_2") (pintype "passive"))
      (node (ref "C40") (pin "2") (pinfunction "2_2") (pintype "passive"))
      (node (ref "C41") (pin "2") (pinfunction "2_2") (pintype "passive"))
      (node (ref "C42") (pin "2") (pinfunction "2_2") (pintype "passive"))
      (node (ref "C43") (pin "2") (pinfunction "2_2") (pintype "passive"))
      (node (ref "C44") (pin "2") (pinfunction "2_2") (pintype "passive"))
      (node (ref "C45") (pin "2") (pinfunction "2_2") (pintype "passive"))
      (node (ref "C46") (pin "2") (pinfunction "2_2") (pintype "passive"))
      (node (ref "C48") (pin "2") (pinfunction "2_2") (pintype "passive"))
      (node (ref "C49") (pin "2") (pinfunction "2_2") (pintype "passive"))
      (node (ref "C5") (pin "2") (pinfunction "2_2") (pintype "passive"))
      (node (ref "C50") (pin "2") (pinfunction "2_2") (pintype "passive"))
      (node (ref "C51") (pin "2") (pinfunction "2_2") (pintype "passive"))
      (node (ref "C6") (pin "2") (pinfunction "2_2") (pintype "passive"))
      (node (ref "C7") (pin "2") (pinfunction "2_2") (pintype "passive"))
      (node (ref "C8") (pin "2") (pinfunction "2_2") (pintype "passive"))
      (node (ref "C9") (pin "2") (pinfunction "2_2") (pintype "passive"))
      (node (ref "J1") (pin "5") (pinfunction "GND_5") (pintype "bidirectional"))
      (node (ref "J1") (pin "G1") (pinfunction "GND_G1") (pintype "bidirectional"))
      (node (ref "J1") (pin "G2") (pinfunction "GND_G2") (pintype "bidirectional"))
      (node (ref "J1") (pin "G3") (pinfunction "GND_G3") (pintype "bidirectional"))
      (node (ref "J1") (pin "G4") (pinfunction "GND_G4") (pintype "bidirectional"))
      (node (ref "J1") (pin "G5") (pinfunction "GND_G5") (pintype "bidirectional"))
      (node (ref "J1") (pin "G6") (pinfunction "GND_G6") (pintype "bidirectional"))
      (node (ref "JPDEBUG") (pin "5") (pinfunction "GND_5") (pintype "bidirectional"))
      (node (ref "R10") (pin "2") (pinfunction "2_2") (pintype "passive"))
      (node (ref "R11") (pin "1") (pinfunction "1_1") (pintype "passive"))
      (node (ref "R32") (pin "2") (pinfunction "2_2") (pintype "passive"))
      (node (ref "R8") (pin "1") (pinfunction "1_1") (pintype "passive"))
      (node (ref "U1") (pin "65") (pinfunction "VSS_65") (pintype "passive"))
      (node (ref "U10") (pin "2") (pinfunction "GND_2") (pintype "passive"))
      (node (ref "U11") (pin "3") (pinfunction "GND1_3") (pintype "bidirectional"))
      (node (ref "U11") (pin "5") (pinfunction "GND2_5") (pintype "bidirectional"))
      (node (ref "U11") (pin "TP") (pinfunction "GND3_TP") (pintype "bidirectional"))
      (node (ref "U12") (pin "2") (pinfunction "GND1_2") (pintype "bidirectional"))
      (node (ref "U12") (pin "TP") (pinfunction "GND2_TP") (pintype "bidirectional"))
      (node (ref "U13") (pin "4") (pinfunction "GND1_4") (pintype "bidirectional"))
      (node (ref "U13") (pin "5") (pinfunction "GND2_5") (pintype "bidirectional"))
      (node (ref "U13") (pin "6") (pinfunction "~{E}_6") (pintype "bidirectional"))
      (node (ref "U15") (pin "1") (pinfunction "A0_1") (pintype "bidirectional"))
      (node (ref "U15") (pin "2") (pinfunction "A1_2") (pintype "bidirectional"))
      (node (ref "U15") (pin "3") (pinfunction "A2_3") (pintype "bidirectional"))
      (node (ref "U15") (pin "4") (pinfunction "GND_4") (pintype "bidirectional"))
      (node (ref "U15") (pin "7") (pinfunction "WP_7") (pintype "bidirectional"))
      (node (ref "U2") (pin "17") (pinfunction "VSS_17_17") (pintype "bidirectional"))
      (node (ref "U2") (pin "18") (pinfunction "VSS_18_18") (pintype "bidirectional"))
      (node (ref "U2") (pin "23") (pinfunction "VSS_23_23") (pintype "bidirectional"))
      (node (ref "U2") (pin "30") (pinfunction "VSS_30_30") (pintype "bidirectional"))
      (node (ref "U2") (pin "31") (pinfunction "VSS_31_31") (pintype "bidirectional"))
      (node (ref "U2") (pin "33") (pinfunction "GND_33") (pintype "bidirectional"))
      (node (ref "U2") (pin "8") (pinfunction "VSS_8_8") (pintype "bidirectional"))
      (node (ref "U3") (pin "10") (pinfunction "RES_10") (pintype "bidirectional"))
      (node (ref "U3") (pin "12") (pinfunction "GND12_12") (pintype "bidirectional"))
      (node (ref "U3") (pin "5") (pinfunction "GND5_5") (pintype "bidirectional"))
      (node (ref "U4") (pin "10") (pinfunction "GND_10_10") (pintype "bidirectional"))
      (node (ref "U4") (pin "5") (pinfunction "GND_5_5") (pintype "bidirectional"))
      (node (ref "U5") (pin "5") (pinfunction "GND_5") (pintype "bidirectional"))
      (node (ref "U6") (pin "1") (pinfunction "S1_1") (pintype "passive"))
      (node (ref "U7") (pin "6") (pinfunction "VSS_6") (pintype "bidirectional"))
      (node (ref "U7") (pin "PGND") (pinfunction "VSS_PGND") (pintype "bidirectional"))
      (node (ref "U8") (pin "6") (pinfunction "GND6_6") (pintype "bidirectional"))
      (node (ref "U8") (pin "7") (pinfunction "GND7_7") (pintype "bidirectional"))
      (node (ref "U9") (pin "6") (pinfunction "GND6_6") (pintype "bidirectional"))
      (node (ref "U9") (pin "7") (pinfunction "GND7_7") (pintype "bidirectional"))
      (node (ref "X2") (pin "2") (pinfunction "GND1_2") (pintype "bidirectional"))
      (node (ref "X2") (pin "4") (pinfunction "GND2_4") (pintype "bidirectional"))
      (node (ref "X4") (pin "2") (pinfunction "GND1_2") (pintype "bidirectional"))
      (node (ref "X4") (pin "4") (pinfunction "GND2_4") (pintype "bidirectional"))
    )
    (net (code "11") (name "I2C1_SCL") (class "Default")
      (node (ref "R1") (pin "1") (pinfunction "1_1") (pintype "passive"))
      (node (ref "U1") (pin "22") (pinfunction "PB12/DAC0_OUT1/OPAMP_OUT1/I2C1_SCL#1/LETIM0_OUT1#1_22") (pintype "bidirectional"))
      (node (ref "U15") (pin "6") (pinfunction "SCL_6") (pintype "bidirectional"))
      (node (ref "U4") (pin "7") (pinfunction "SCL_7") (pintype "bidirectional"))
      (node (ref "U5") (pin "2") (pinfunction "SCL_2") (pintype "bidirectional"))
    )
    (net (code "12") (name "I2C1_SDA") (class "Default")
      (node (ref "R9") (pin "1") (pinfunction "1_1") (pintype "passive"))
      (node (ref "U1") (pin "21") (pinfunction "PB11/DAC0_OUT0/OPAMP_OUT0/I2C1_SDA#1/LETIM0_OUT0#1/TIM1_CC2#3_21") (pintype "bidirectional"))
      (node (ref "U15") (pin "5") (pinfunction "SDA_5") (pintype "bidirectional"))
      (node (ref "U4") (pin "6") (pinfunction "SDA_6") (pintype "bidirectional"))
      (node (ref "U5") (pin "3") (pinfunction "SDA_3") (pintype "bidirectional"))
    )
    (net (code "13") (name "LED1") (class "Default")
      (node (ref "R20") (pin "1") (pinfunction "1_1") (pintype "passive"))
      (node (ref "U1") (pin "60") (pinfunction "PE12/CMU_CLK1#2/I2C0_SDA#6/LES_ALTEX6/TIM1_CC2#1/US0_CLK#0/US0_RX#3_60") (pintype "bidirectional"))
    )
    (net (code "14") (name "LED2") (class "Default")
      (node (ref "R23") (pin "1") (pinfunction "1_1") (pintype "passive"))
      (node (ref "U1") (pin "61") (pinfunction "PE13/ACMP0_O#0/GPIO_EM4WU5/I2C0_SCL#6/LES_ALTEX7/US0_CS#0/US0_TX#3_61") (pintype "bidirectional"))
    )
    (net (code "15") (name "LED3") (class "Default")
      (node (ref "R19") (pin "1") (pinfunction "1_1") (pintype "passive"))
      (node (ref "U1") (pin "62") (pinfunction "PE14/LEU0_TX#2/TIM3_CC0_62") (pintype "bidirectional"))
    )
    (net (code "16") (name "LED4") (class "Default")
      (node (ref "R22") (pin "1") (pinfunction "1_1") (pintype "passive"))
      (node (ref "U1") (pin "63") (pinfunction "PE15/LEU0_RX#2/TIM3_CC1_63") (pintype "bidirectional"))
    )
    (net (code "17") (name "LED5") (class "Default")
      (node (ref "R18") (pin "1") (pinfunction "1_1") (pintype "passive"))
      (node (ref "U1") (pin "9") (pinfunction "PC0/ACMP0_CH0/DAC0_OUT0ALT/OPAMP_OUT0ALT#0/I2C0_SDA#4/LES_CH0/PCNT0_S0IN#2/PRS_CH2#0/TIM0_CC1#4/US0_TX#5/US1_TX#0_9") (pintype "bidirectional"))
    )
    (net (code "18") (name "LED6") (class "Default")
      (node (ref "R21") (pin "1") (pinfunction "1_1") (pintype "passive"))
      (node (ref "U1") (pin "10") (pinfunction "PC1/ACMP0_CH1/DAC0_OUT0ALT/OPAMP_OUT0ALT#1/I2C0_SCL#4/LES_CH1/PCNT0_S1IN#2/PRS_CH3#0/TIM0_CC2#4/US0_RX#5/US1_RX#0_10") (pintype "bidirectional"))
    )
    (net (code "19") (name "LED7") (class "Default")
      (node (ref "R17") (pin "1") (pinfunction "1_1") (pintype "passive"))
      (node (ref "U1") (pin "11") (pinfunction "PC2/ACMP0_CH2/DAC0_OUT0ALT/OPAMP_OUT0ALT#2/LES_CH2/TIM0_CDTI0#4/US2_TX_11") (pintype "bidirectional"))
    )
    (net (code "20") (name "LED8") (class "Default")
      (node (ref "R6") (pin "1") (pinfunction "1_1") (pintype "passive"))
      (node (ref "U1") (pin "12") (pinfunction "PC3/ACMP0_CH3/DAC0_OUT0ALT/OPAMP_OUT0ALT#3/LES_CH3/TIM0_CDTI1#4/US2_RX_12") (pintype "bidirectional"))
    )
    (net (code "21") (name "LED_EN") (class "Default")
      (node (ref "U1") (pin "17") (pinfunction "PA8/TIM2_CC0#0_17") (pintype "bidirectional"))
      (node (ref "U5") (pin "4") (pinfunction "EN_4") (pintype "bidirectional"))
    )
    (net (code "22") (name "MAG_INT") (class "Default")
      (node (ref "U1") (pin "19") (pinfunction "PA10/TIM2_CC2#0_19") (pintype "bidirectional"))
      (node (ref "U4") (pin "9") (pinfunction "INT1_9") (pintype "bidirectional"))
    )
    (net (code "23") (name "NRF_PWR") (class "Default")
      (node (ref "U1") (pin "38") (pinfunction "PC7/ACMP0_CH7/ETM_TD0#2/I2C0_SCL#2/LES_CH7/LEU1_RX#0_38") (pintype "bidirectional"))
      (node (ref "U8") (pin "1") (pinfunction "ON_1") (pintype "bidirectional"))
    )
    (net (code "24") (name "NRF_RDYN") (class "Default")
      (node (ref "U1") (pin "32") (pinfunction "PD4/ADC0_CH4/DAC0_P2/OPAMP_P2/ETM_TD2#0,2/LEU0_TX#0_32") (pintype "bidirectional"))
      (node (ref "U2") (pin "16") (pinfunction "RDYN_16") (pintype "bidirectional"))
    )
    (net (code "25") (name "NRF_REQN") (class "Default")
      (node (ref "U1") (pin "31") (pinfunction "PD3/ADC0_CH3/DAC0_N2/OPAMP_N2/ETM_TD1#0,2/TIM0_CC2#3/US1_CS#1_31") (pintype "bidirectional"))
      (node (ref "U2") (pin "12") (pinfunction "REQN_12") (pintype "bidirectional"))
    )
    (net (code "26") (name "NRF_RESETN") (class "Default")
      (node (ref "U1") (pin "33") (pinfunction "PD5/ADC0_CH5/DAC0_OUT2/OPAMP_OUT2#0/ETM_TD3#0,2/LEU0_RX#0_33") (pintype "bidirectional"))
      (node (ref "U2") (pin "19") (pinfunction "RESETN_19") (pintype "bidirectional"))
    )
    (net (code "27") (name "Net-(A1-A)") (class "Default")
      (node (ref "A1") (pin "FP") (pinfunction "A_FP") (pintype "bidirectional"))
      (node (ref "C7") (pin "1") (pinfunction "1_1") (pintype "passive"))
      (node (ref "L6") (pin "2") (pinfunction "2_2") (pintype "passive"))
    )
    (net (code "28") (name "Net-(B+-Pad1)") (class "Default")
      (node (ref "B+") (pin "1") (pinfunction "1_1") (pintype "bidirectional"))
      (node (ref "B1") (pin "+") (pinfunction "+_+") (pintype "passive"))
      (node (ref "BAT1") (pin "1") (pinfunction "1_1") (pintype "bidirectional"))
      (node (ref "R2") (pin "2") (pinfunction "2_2") (pintype "passive"))
    )
    (net (code "29") (name "Net-(C4-Pad1)") (class "Default")
      (node (ref "C4") (pin "1") (pinfunction "1_1") (pintype "passive"))
      (node (ref "R12") (pin "2") (pinfunction "2_2") (pintype "passive"))
      (node (ref "U7") (pin "3") (pinfunction "VBAT_3") (pintype "bidirectional"))
      (node (ref "U7") (pin "4") (pinfunction "VBAT_4") (pintype "bidirectional"))
    )
    (net (code "30") (name "Net-(C46-Pad1)") (class "Default")
      (node (ref "C46") (pin "1") (pinfunction "1_1") (pintype "passive"))
      (node (ref "C47") (pin "2") (pinfunction "2_2") (pintype "passive"))
      (node (ref "C6") (pin "1") (pinfunction "1_1") (pintype "passive"))
      (node (ref "L6") (pin "1") (pinfunction "1_1") (pintype "passive"))
    )
    (net (code "31") (name "Net-(C47-Pad1)") (class "Default")
      (node (ref "C47") (pin "1") (pinfunction "1_1") (pintype "passive"))
      (node (ref "L3") (pin "2") (pinfunction "2_2") (pintype "passive"))
    )
    (net (code "32") (name "Net-(D0-B)") (class "Default")
      (node (ref "D0") (pin "3") (pinfunction "B_3") (pintype "passive"))
      (node (ref "R29") (pin "2") (pinfunction "2_2") (pintype "passive"))
    )
    (net (code "33") (name "Net-(D0-G)") (class "Default")
      (node (ref "D0") (pin "4") (pinfunction "G_4") (pintype "passive"))
      (node (ref "R30") (pin "2") (pinfunction "2_2") (pintype "passive"))
    )
    (net (code "34") (name "Net-(D0-R)") (class "Default")
      (node (ref "D0") (pin "2") (pinfunction "R_2") (pintype "passive"))
      (node (ref "R4") (pin "2") (pinfunction "2_2") (pintype "passive"))
    )
    (net (code "35") (name "Net-(D1-PadC)") (class "Default")
      (node (ref "D1") (pin "C") (pinfunction "C_C") (pintype "passive"))
      (node (ref "R20") (pin "2") (pinfunction "2_2") (pintype "passive"))
    )
    (net (code "36") (name "Net-(D2-PadC)") (class "Default")
      (node (ref "D2") (pin "C") (pinfunction "C_C") (pintype "passive"))
      (node (ref "R23") (pin "2") (pinfunction "2_2") (pintype "passive"))
    )
    (net (code "37") (name "Net-(D3-PadC)") (class "Default")
      (node (ref "D3") (pin "C") (pinfunction "C_C") (pintype "passive"))
      (node (ref "R19") (pin "2") (pinfunction "2_2") (pintype "passive"))
    )
    (net (code "38") (name "Net-(D4-PadC)") (class "Default")
      (node (ref "D4") (pin "C") (pinfunction "C_C") (pintype "passive"))
      (node (ref "R22") (pin "2") (pinfunction "2_2") (pintype "passive"))
    )
    (net (code "39") (name "Net-(D5-PadC)") (class "Default")
      (node (ref "D5") (pin "C") (pinfunction "C_C") (pintype "passive"))
      (node (ref "R18") (pin "2") (pinfunction "2_2") (pintype "passive"))
    )
    (net (code "40") (name "Net-(D6-PadC)") (class "Default")
      (node (ref "D6") (pin "C") (pinfunction "C_C") (pintype "passive"))
      (node (ref "R21") (pin "2") (pinfunction "2_2") (pintype "passive"))
    )
    (net (code "41") (name "Net-(D7-PadC)") (class "Default")
      (node (ref "D7") (pin "C") (pinfunction "C_C") (pintype "passive"))
      (node (ref "R17") (pin "2") (pinfunction "2_2") (pintype "passive"))
    )
    (net (code "42") (name "Net-(D8-PadC)") (class "Default")
      (node (ref "D8") (pin "C") (pinfunction "C_C") (pintype "passive"))
      (node (ref "R6") (pin "2") (pinfunction "2_2") (pintype "passive"))
    )
    (net (code "43") (name "Net-(D9-B)") (class "Default")
      (node (ref "D9") (pin "3") (pinfunction "B_3") (pintype "passive"))
      (node (ref "R16") (pin "2") (pinfunction "2_2") (pintype "passive"))
    )
    (net (code "44") (name "Net-(D9-G)") (class "Default")
      (node (ref "D9") (pin "4") (pinfunction "G_4") (pintype "passive"))
      (node (ref "R26") (pin "2") (pinfunction "2_2") (pintype "passive"))
    )
    (net (code "45") (name "Net-(D9-R)") (class "Default")
      (node (ref "D9") (pin "2") (pinfunction "R_2") (pintype "passive"))
      (node (ref "R24") (pin "2") (pinfunction "2_2") (pintype "passive"))
    )
    (net (code "46") (name "Net-(D10-PadA)") (class "Default")
      (node (ref "D10") (pin "A") (pinfunction "A_A") (pintype "passive"))
      (node (ref "L9") (pin "2") (pinfunction "2_2") (pintype "passive"))
    )
    (net (code "47") (name "Net-(J1-5V)") (class "Default")
      (node (ref "J1") (pin "1") (pinfunction "5V_1") (pintype "bidirectional"))
      (node (ref "L9") (pin "1") (pinfunction "1_1") (pintype "passive"))
      (node (ref "U10") (pin "5") (pinfunction "VBUS_5") (pintype "passive"))
      (node (ref "USBV") (pin "1") (pinfunction "1_1") (pintype "bidirectional"))
    )
    (net (code "48") (name "Net-(J1-D+)") (class "Default")
      (node (ref "J1") (pin "3") (pinfunction "D+_3") (pintype "bidirectional"))
      (node (ref "R28") (pin "1") (pinfunction "1_1") (pintype "passive"))
      (node (ref "U10") (pin "1") (pinfunction "IO1_1") (pintype "passive"))
      (node (ref "U10") (pin "6") (pinfunction "IO1_6") (pintype "passive"))
      (node (ref "USBD+") (pin "1") (pinfunction "1_1") (pintype "bidirectional"))
    )
    (net (code "49") (name "Net-(J1-D-)") (class "Default")
      (node (ref "J1") (pin "2") (pinfunction "D-_2") (pintype "bidirectional"))
      (node (ref "R27") (pin "1") (pinfunction "1_1") (pintype "passive"))
      (node (ref "U10") (pin "3") (pinfunction "IO2_3") (pintype "passive"))
      (node (ref "U10") (pin "4") (pinfunction "IO2_4") (pintype "passive"))
      (node (ref "USBD-") (pin "1") (pinfunction "1_1") (pintype "bidirectional"))
    )
    (net (code "50") (name "Net-(JPDEBUG-NRESET)") (class "Default")
      (node (ref "JPDEBUG") (pin "3") (pinfunction "NRESET_3") (pintype "bidirectional"))
      (node (ref "U1") (pin "20") (pinfunction "RESETN_20") (pintype "passive"))
    )
    (net (code "51") (name "Net-(JPDEBUG-SWCLK)") (class "Default")
      (node (ref "JPDEBUG") (pin "4") (pinfunction "SWCLK_4") (pintype "bidirectional"))
      (node (ref "U1") (pin "49") (pinfunction "PF0/DBG_SWCLK#0,1,2,3/I2C0_SDA#5/LETIM0_OUT0#2/LEU0_TX#3/TIM0_CC0#5/US1_CLK#2_49") (pintype "bidirectional"))
    )
    (net (code "52") (name "Net-(JPDEBUG-SWDIO)") (class "Default")
      (node (ref "JPDEBUG") (pin "2") (pinfunction "SWDIO_2") (pintype "bidirectional"))
      (node (ref "U1") (pin "50") (pinfunction "PF1/DBG_SWDIO#0,1,2,3/GPIO_EM4WU3/I2C0_SCL#5/LETIM0_OUT1#2/LEU0_RX#3/TIM0_CC1#5/US1_CS#2_50") (pintype "bidirectional"))
    )
    (net (code "53") (name "Net-(L4-Pad2)") (class "Default")
      (node (ref "L4") (pin "2") (pinfunction "2_2") (pintype "passive"))
      (node (ref "L5") (pin "1") (pinfunction "1_1") (pintype "passive"))
    )
    (net (code "54") (name "Net-(U1B-PB7{slash}LFXTAL_P{slash}TIM1_CC0#3{slash}US0_TX#4{slash}US1_CLK#0)") (class "Default")
      (node (ref "C33") (pin "1") (pinfunction "1_1") (pintype "passive"))
      (node (ref "U1") (pin "15") (pinfunction "PB7/LFXTAL_P/TIM1_CC0#3/US0_TX#4/US1_CLK#0_15") (pintype "bidirectional"))
      (node (ref "X1") (pin "1") (pinfunction "1_1") (pintype "passive"))
    )
    (net (code "55") (name "Net-(U1B-PB8{slash}LFXTAL_N{slash}TIM1_CC1#3{slash}US0_RX#4{slash}US1_CS#0)") (class "Default")
      (node (ref "C32") (pin "1") (pinfunction "1_1") (pintype "passive"))
      (node (ref "U1") (pin "16") (pinfunction "PB8/LFXTAL_N/TIM1_CC1#3/US0_RX#4/US1_CS#0_16") (pintype "bidirectional"))
      (node (ref "X1") (pin "2") (pinfunction "2_2") (pintype "passive"))
    )
    (net (code "56") (name "Net-(U1B-PB13{slash}HFXTAL_P{slash}LEU0_TX#1{slash}US0_CLK#4,5)") (class "Default")
      (node (ref "C22") (pin "1") (pinfunction "1_1") (pintype "passive"))
      (node (ref "U1") (pin "24") (pinfunction "PB13/HFXTAL_P/LEU0_TX#1/US0_CLK#4,5_24") (pintype "bidirectional"))
      (node (ref "X4") (pin "1") (pinfunction "1_1") (pintype "passive"))
    )
    (net (code "57") (name "Net-(U1B-PB14{slash}HFXTAL_N{slash}LEU0_RX#1{slash}US0_CS#4,5)") (class "Default")
      (node (ref "C48") (pin "1") (pinfunction "1_1") (pintype "passive"))
      (node (ref "U1") (pin "25") (pinfunction "PB14/HFXTAL_N/LEU0_RX#1/US0_CS#4,5_25") (pintype "bidirectional"))
      (node (ref "X4") (pin "3") (pinfunction "2_3") (pintype "passive"))
    )
    (net (code "58") (name "Net-(U1G-AVDD_0)") (class "Default")
      (node (ref "C25") (pin "1") (pinfunction "1_1") (pintype "passive"))
      (node (ref "C26") (pin "1") (pinfunction "1_1") (pintype "passive"))
      (node (ref "C27") (pin "1") (pinfunction "1_1") (pintype "passive"))
      (node (ref "C28") (pin "1") (pinfunction "1_1") (pintype "passive"))
      (node (ref "C29") (pin "1") (pinfunction "1_1") (pintype "passive"))
      (node (ref "C30") (pin "1") (pinfunction "1_1") (pintype "passive"))
      (node (ref "C31") (pin "1") (pinfunction "1_1") (pintype "passive"))
      (node (ref "R25") (pin "1") (pinfunction "1_1") (pintype "passive"))
      (node (ref "U1") (pin "23") (pinfunction "AVDD_1_23") (pintype "passive"))
      (node (ref "U1") (pin "26") (pinfunction "IOVDD_3_26") (pintype "passive"))
      (node (ref "U1") (pin "27") (pinfunction "AVDD_0_27") (pintype "passive"))
      (node (ref "U1") (pin "39") (pinfunction "VDD_DREG_39") (pintype "passive"))
      (node (ref "U1") (pin "55") (pinfunction "IOVDD_5_55") (pintype "passive"))
      (node (ref "U1") (pin "8") (pinfunction "IOVDD_0_8") (pintype "passive"))
    )
    (net (code "59") (name "Net-(U1G-DECOUPLE)") (class "Default")
      (node (ref "C24") (pin "1") (pinfunction "1_1") (pintype "passive"))
      (node (ref "U1") (pin "40") (pinfunction "DECOUPLE_40") (pintype "passive"))
    )
    (net (code "60") (name "Net-(U1G-USB_VREGO)") (class "Default")
      (node (ref "C8") (pin "1") (pinfunction "1_1") (pintype "passive"))
      (node (ref "U1") (pin "46") (pinfunction "USB_VREGO_46") (pintype "passive"))
    )
    (net (code "61") (name "Net-(U2-ANT1)") (class "Default")
      (node (ref "L1") (pin "1") (pinfunction "1_1") (pintype "passive"))
      (node (ref "L2") (pin "2") (pinfunction "2_2") (pintype "passive"))
      (node (ref "U2") (pin "21") (pinfunction "ANT1_21") (pintype "bidirectional"))
    )
    (net (code "62") (name "Net-(U2-ANT2)") (class "Default")
      (node (ref "L1") (pin "2") (pinfunction "2_2") (pintype "passive"))
      (node (ref "L3") (pin "1") (pinfunction "1_1") (pintype "passive"))
      (node (ref "U2") (pin "22") (pinfunction "ANT2_22") (pintype "bidirectional"))
    )
    (net (code "63") (name "Net-(U2-AVDD_24)") (class "Default")
      (node (ref "C38") (pin "1") (pinfunction "1_1") (pintype "passive"))
      (node (ref "C39") (pin "1") (pinfunction "1_1") (pintype "passive"))
      (node (ref "C42") (pin "1") (pinfunction "1_1") (pintype "passive"))
      (node (ref "C43") (pin "1") (pinfunction "1_1") (pintype "passive"))
      (node (ref "C9") (pin "1") (pinfunction "1_1") (pintype "passive"))
      (node (ref "L5") (pin "2") (pinfunction "2_2") (pintype "passive"))
      (node (ref "R7") (pin "1") (pinfunction "1_1") (pintype "passive"))
      (node (ref "U2") (pin "1") (pinfunction "VDD_1_1") (pintype "bidirectional"))
      (node (ref "U2") (pin "24") (pinfunction "AVDD_24_24") (pintype "bidirectional"))
      (node (ref "U2") (pin "26") (pinfunction "AVDD_26_26") (pintype "bidirectional"))
      (node (ref "U2") (pin "29") (pinfunction "AVDD_29_29") (pintype "bidirectional"))
      (node (ref "U2") (pin "9") (pinfunction "VDD_9_9") (pintype "bidirectional"))
      (node (ref "U8") (pin "4") (pinfunction "VOUT4_4") (pintype "bidirectional"))
      (node (ref "U8") (pin "5") (pinfunction "VOUT5_5") (pintype "bidirectional"))
    )
    (net (code "64") (name "Net-(U2-DCC)") (class "Default")
      (node (ref "L4") (pin "1") (pinfunction "1_1") (pintype "passive"))
      (node (ref "U2") (pin "32") (pinfunction "DCC_32") (pintype "bidirectional"))
    )
    (net (code "65") (name "Net-(U2-DEC1)") (class "Default")
      (node (ref "C41") (pin "1") (pinfunction "1_1") (pintype "passive"))
      (node (ref "U2") (pin "2") (pinfunction "DEC1_2") (pintype "bidirectional"))
    )
    (net (code "66") (name "Net-(U2-DEC2)") (class "Default")
      (node (ref "C40") (pin "1") (pinfunction "1_1") (pintype "passive"))
      (node (ref "U2") (pin "3") (pinfunction "DEC2_3") (pintype "bidirectional"))
    )
    (net (code "67") (name "Net-(U2-IREF)") (class "Default")
      (node (ref "R11") (pin "2") (pinfunction "2_2") (pintype "passive"))
      (node (ref "U2") (pin "25") (pinfunction "IREF_25") (pintype "bidirectional"))
    )
    (net (code "68") (name "Net-(U2-VDD_PA)") (class "Default")
      (node (ref "C44") (pin "1") (pinfunction "1_1") (pintype "passive"))
      (node (ref "C45") (pin "1") (pinfunction "1_1") (pintype "passive"))
      (node (ref "L2") (pin "1") (pinfunction "1_1") (pintype "passive"))
      (node (ref "U2") (pin "20") (pinfunction "VDD_PA_20") (pintype "bidirectional"))
    )
    (net (code "69") (name "Net-(U2-XC1)") (class "Default")
      (node (ref "C35") (pin "1") (pinfunction "1_1") (pintype "passive"))
      (node (ref "U2") (pin "28") (pinfunction "XC1_28") (pintype "bidirectional"))
      (node (ref "X2") (pin "1") (pinfunction "1_1") (pintype "passive"))
    )
    (net (code "70") (name "Net-(U2-XC2)") (class "Default")
      (node (ref "C34") (pin "1") (pinfunction "1_1") (pintype "passive"))
      (node (ref "U2") (pin "27") (pinfunction "XC2_27") (pintype "bidirectional"))
      (node (ref "X2") (pin "3") (pinfunction "2_3") (pintype "passive"))
    )
    (net (code "71") (name "Net-(U2-XL1)") (class "Default")
      (node (ref "C37") (pin "1") (pinfunction "1_1") (pintype "passive"))
      (node (ref "U2") (pin "5") (pinfunction "XL1_5") (pintype "bidirectional"))
      (node (ref "X3") (pin "1") (pinfunction "1_1") (pintype "passive"))
    )
    (net (code "72") (name "Net-(U2-XL2)") (class "Default")
      (node (ref "C36") (pin "1") (pinfunction "1_1") (pintype "passive"))
      (node (ref "U2") (pin "4") (pinfunction "XL2_4") (pintype "bidirectional"))
      (node (ref "X3") (pin "2") (pinfunction "2_2") (pintype "passive"))
    )
    (net (code "73") (name "Net-(U4-CAP-A)") (class "Default")
      (node (ref "C16") (pin "1") (pinfunction "1_1") (pintype "passive"))
      (node (ref "U4") (pin "1") (pinfunction "CAP-A_1") (pintype "bidirectional"))
    )
    (net (code "74") (name "Net-(U4-CAP-R)") (class "Default")
      (node (ref "C17") (pin "1") (pinfunction "1_1") (pintype "passive"))
      (node (ref "U4") (pin "4") (pinfunction "CAP-R_4") (pintype "bidirectional"))
    )
    (net (code "75") (name "Net-(U5-P1)") (class "Default")
      (node (ref "R16") (pin "1") (pinfunction "1_1") (pintype "passive"))
      (node (ref "U5") (pin "7") (pinfunction "P1_7") (pintype "bidirectional"))
    )
    (net (code "76") (name "Net-(U5-P2)") (class "Default")
      (node (ref "R26") (pin "1") (pinfunction "1_1") (pintype "passive"))
      (node (ref "U5") (pin "8") (pinfunction "P2_8") (pintype "bidirectional"))
    )
    (net (code "77") (name "Net-(U5-P3)") (class "Default")
      (node (ref "R24") (pin "1") (pinfunction "1_1") (pintype "passive"))
      (node (ref "U5") (pin "9") (pinfunction "P3_9") (pintype "bidirectional"))
    )
    (net (code "78") (name "Net-(U5-P4)") (class "Default")
      (node (ref "R29") (pin "1") (pinfunction "1_1") (pintype "passive"))
      (node (ref "U5") (pin "10") (pinfunction "P4_10") (pintype "bidirectional"))
    )
    (net (code "79") (name "Net-(U5-P5)") (class "Default")
      (node (ref "R30") (pin "1") (pinfunction "1_1") (pintype "passive"))
      (node (ref "U5") (pin "11") (pinfunction "P5_11") (pintype "bidirectional"))
    )
    (net (code "80") (name "Net-(U5-P6)") (class "Default")
      (node (ref "R4") (pin "1") (pinfunction "1_1") (pintype "passive"))
      (node (ref "U5") (pin "12") (pinfunction "P6_12") (pintype "bidirectional"))
    )
    (net (code "81") (name "Net-(U6-D1)") (class "Default")
      (node (ref "R33") (pin "2") (pinfunction "2_2") (pintype "passive"))
      (node (ref "U6") (pin "5") (pinfunction "G2_5") (pintype "passive"))
      (node (ref "U6") (pin "6") (pinfunction "D1_6") (pintype "passive"))
    )
    (net (code "82") (name "Net-(U6-S2)") (class "Default")
      (node (ref "R31") (pin "1") (pinfunction "1_1") (pintype "passive"))
      (node (ref "U6") (pin "4") (pinfunction "S2_4") (pintype "passive"))
    )
    (net (code "83") (name "Net-(U11-OUT)") (class "Default")
      (node (ref "C21") (pin "1") (pinfunction "1_1") (pintype "passive"))
      (node (ref "R14") (pin "2") (pinfunction "2_2") (pintype "passive"))
      (node (ref "U11") (pin "1") (pinfunction "OUT_1") (pintype "bidirectional"))
      (node (ref "U13") (pin "1") (pinfunction "Y0_1") (pintype "bidirectional"))
      (node (ref "U13") (pin "8") (pinfunction "VCC_8") (pintype "bidirectional"))
    )
    (net (code "84") (name "Net-(U12-FB)") (class "Default")
      (node (ref "R10") (pin "1") (pinfunction "1_1") (pintype "passive"))
      (node (ref "R3") (pin "2") (pinfunction "2_2") (pintype "passive"))
      (node (ref "U12") (pin "4") (pinfunction "FB_4") (pintype "bidirectional"))
    )
    (net (code "85") (name "Net-(U12-PG)") (class "Default")
      (node (ref "R13") (pin "1") (pinfunction "1_1") (pintype "passive"))
      (node (ref "U12") (pin "6") (pinfunction "PG_6") (pintype "bidirectional"))
      (node (ref "U13") (pin "3") (pinfunction "S_3") (pintype "bidirectional"))
    )
    (net (code "86") (name "Net-(U12-SW)") (class "Default")
      (node (ref "L7") (pin "1") (pinfunction "1_1") (pintype "passive"))
      (node (ref "U12") (pin "7") (pinfunction "SW_7") (pintype "bidirectional"))
    )
    (net (code "87") (name "Net-(U12-VOS)") (class "Default")
      (node (ref "C19") (pin "1") (pinfunction "1_1") (pintype "passive"))
      (node (ref "L7") (pin "2") (pinfunction "2_2") (pintype "passive"))
      (node (ref "R13") (pin "2") (pinfunction "2_2") (pintype "passive"))
      (node (ref "R3") (pin "1") (pinfunction "1_1") (pintype "passive"))
      (node (ref "U12") (pin "5") (pinfunction "VOS_5") (pintype "bidirectional"))
      (node (ref "U13") (pin "2") (pinfunction "Y1_2") (pintype "bidirectional"))
    )
    (net (code "88") (name "PWR_HIGH") (class "Default")
      (node (ref "U1") (pin "54") (pinfunction "PF5/PRS_CH2#1/TIM0_CDTI2#2,5/USB_VBUSEN_54") (pintype "bidirectional"))
      (node (ref "U12") (pin "1") (pinfunction "EN_1") (pintype "bidirectional"))
    )
    (net (code "89") (name "PWR_MODE") (class "Default")
      (node (ref "U1") (pin "53") (pinfunction "PF12/USB_ID_53") (pintype "bidirectional"))
      (node (ref "U12") (pin "3") (pinfunction "MODE_3") (pintype "bidirectional"))
    )
    (net (code "90") (name "US0_CLK") (class "Default")
      (node (ref "U1") (pin "42") (pinfunction "PC9/ACMP1_CH1/GPIO_EM4WU2/LES_CH9/TIM2_CC1#2/US0_CLK#2_42") (pintype "bidirectional"))
      (node (ref "U3") (pin "4") (pinfunction "SPC_4") (pintype "bidirectional"))
    )
    (net (code "91") (name "US0_MISO") (class "Default")
      (node (ref "U1") (pin "43") (pinfunction "PC10/ACMP1_CH2/LES_CH10/TIM2_CC2#2/US0_RX#2_43") (pintype "bidirectional"))
      (node (ref "U3") (pin "7") (pinfunction "SDO_7") (pintype "bidirectional"))
    )
    (net (code "92") (name "US0_MOSI") (class "Default")
      (node (ref "U1") (pin "44") (pinfunction "PC11/ACMP1_CH3/LES_CH11/US0_TX#2_44") (pintype "bidirectional"))
      (node (ref "U3") (pin "6") (pinfunction "SDI_6") (pintype "bidirectional"))
    )
    (net (code "93") (name "US1_CLK") (class "Default")
      (node (ref "U1") (pin "30") (pinfunction "PD2/ADC0_CH2/DBG_SWO#3/TIM0_CC1#3/US1_CLK#1/USB_DMPU_30") (pintype "bidirectional"))
      (node (ref "U2") (pin "11") (pinfunction "SCK_11") (pintype "bidirectional"))
    )
    (net (code "94") (name "US1_MISO") (class "Default")
      (node (ref "U1") (pin "29") (pinfunction "PD1/ADC0_CH1/DAC0_OUT1ALT/OPAMP_OUT1ALT#4/DBG_SWO#2/PCNT2_S1IN#0/TIM0_CC0#3/US1_RX#1_29") (pintype "bidirectional"))
      (node (ref "U2") (pin "14") (pinfunction "MISO_14") (pintype "bidirectional"))
    )
    (net (code "95") (name "US1_MOSI") (class "Default")
      (node (ref "U1") (pin "28") (pinfunction "PD0/ADC0_CH0/DAC0_OUT0ALT/OPAMP_OUT0ALT#4/DAC0_OUT2/OPAMP_OUT2#1/PCNT2_S0IN#0/US1_TX#1_28") (pintype "bidirectional"))
      (node (ref "U2") (pin "13") (pinfunction "MOSI_13") (pintype "bidirectional"))
    )
    (net (code "96") (name "USB_DM") (class "Default")
      (node (ref "R27") (pin "2") (pinfunction "2_2") (pintype "passive"))
      (node (ref "U1") (pin "47") (pinfunction "PF10/USB_DM_47") (pintype "bidirectional"))
    )
    (net (code "97") (name "USB_DP") (class "Default")
      (node (ref "R28") (pin "2") (pinfunction "2_2") (pintype "passive"))
      (node (ref "U1") (pin "48") (pinfunction "PF11/USB_DP_48") (pintype "bidirectional"))
    )
    (net (code "98") (name "USB_VBUS") (class "Default")
      (node (ref "C15") (pin "1") (pinfunction "1_1") (pintype "passive"))
      (node (ref "C5") (pin "1") (pinfunction "1_1") (pintype "passive"))
      (node (ref "D10") (pin "C") (pinfunction "C_C") (pintype "passive"))
      (node (ref "U1") (pin "45") (pinfunction "USB_VREGI_45") (pintype "passive"))
      (node (ref "U1") (pin "52") (pinfunction "USB_VBUS_52") (pintype "passive"))
      (node (ref "U14") (pin "1") (pinfunction "A_1") (pintype "passive"))
      (node (ref "U14") (pin "5") (pinfunction "G_5") (pintype "passive"))
      (node (ref "U7") (pin "1") (pinfunction "VDD_1") (pintype "bidirectional"))
      (node (ref "U7") (pin "2") (pinfunction "VDD_2") (pintype "bidirectional"))
    )
    (net (code "99") (name "VCC") (class "Default")
      (node (ref "C1") (pin "1") (pinfunction "1_1") (pintype "passive"))
      (node (ref "C10") (pin "1") (pinfunction "1_1") (pintype "passive"))
      (node (ref "C11") (pin "1") (pinfunction "1_1") (pintype "passive"))
      (node (ref "C23") (pin "1") (pinfunction "1_1") (pintype "passive"))
      (node (ref "C3") (pin "1") (pinfunction "1_1") (pintype "passive"))
      (node (ref "D1") (pin "A") (pinfunction "A_A") (pintype "passive"))
      (node (ref "D2") (pin "A") (pinfunction "A_A") (pintype "passive"))
      (node (ref "D3") (pin "A") (pinfunction "A_A") (pintype "passive"))
      (node (ref "D4") (pin "A") (pinfunction "A_A") (pintype "passive"))
      (node (ref "D5") (pin "A") (pinfunction "A_A") (pintype "passive"))
      (node (ref "D6") (pin "A") (pinfunction "A_A") (pintype "passive"))
      (node (ref "D7") (pin "A") (pinfunction "A_A") (pintype "passive"))
      (node (ref "D8") (pin "A") (pinfunction "A_A") (pintype "passive"))
      (node (ref "JPDEBUG") (pin "1") (pinfunction "VCC_1") (pintype "bidirectional"))
      (node (ref "R14") (pin "1") (pinfunction "1_1") (pintype "passive"))
      (node (ref "R15") (pin "1") (pinfunction "1_1") (pintype "passive"))
      (node (ref "R25") (pin "2") (pinfunction "2_2") (pintype "passive"))
      (node (ref "R5") (pin "2") (pinfunction "2_2") (pintype "passive"))
      (node (ref "R7") (pin "2") (pinfunction "2_2") (pintype "passive"))
      (node (ref "U13") (pin "7") (pinfunction "Z_7") (pintype "bidirectional"))
      (node (ref "U3") (pin "1") (pinfunction "VDD_IO_1") (pintype "bidirectional"))
      (node (ref "U3") (pin "14") (pinfunction "VDD_14") (pintype "bidirectional"))
      (node (ref "U8") (pin "2") (pinfunction "VIN2_2") (pintype "bidirectional"))
      (node (ref "U8") (pin "3") (pinfunction "VIN3_3") (pintype "bidirectional"))
      (node (ref "U9") (pin "2") (pinfunction "VIN2_2") (pintype "bidirectional"))
      (node (ref "U9") (pin "3") (pinfunction "VIN3_3") (pintype "bidirectional"))
    )
    (net (code "100") (name "VUNREG") (class "Default")
      (node (ref "C18") (pin "1") (pinfunction "1_1") (pintype "passive"))
      (node (ref "C20") (pin "1") (pinfunction "1_1") (pintype "passive"))
      (node (ref "D0") (pin "1") (pinfunction "A_1") (pintype "passive"))
      (node (ref "D9") (pin "1") (pinfunction "A_1") (pintype "passive"))
      (node (ref "U11") (pin "4") (pinfunction "EN_4") (pintype "bidirectional"))
      (node (ref "U11") (pin "6") (pinfunction "IN_6") (pintype "bidirectional"))
      (node (ref "U12") (pin "8") (pinfunction "VIN_8") (pintype "bidirectional"))
      (node (ref "U14") (pin "3") (pinfunction "D_3") (pintype "passive"))
      (node (ref "U14") (pin "6") (pinfunction "C_6") (pintype "passive"))
      (node (ref "U14") (pin "C") (pinfunction "C_C") (pintype "passive"))
      (node (ref "U14") (pin "D") (pinfunction "D_D") (pintype "passive"))
    )
    (net (code "101") (name "unconnected-(J1-ID-Pad4)") (class "Default")
      (node (ref "J1") (pin "4") (pinfunction "ID_4") (pintype "bidirectional"))
    )
    (net (code "102") (name "unconnected-(JPDEBUG-SWO-Pad6)") (class "Default")
      (node (ref "JPDEBUG") (pin "6") (pinfunction "SWO_6") (pintype "bidirectional"))
    )
    (net (code "103") (name "unconnected-(U1A-PA0{slash}GPIO_EM4WU0{slash}I2C0_SDA#0{slash}LEU0_RX#4{slash}PRS_CH0{slash}TIM0_CC0#0,1,4-Pad1)") (class "Default")
      (node (ref "U1") (pin "1") (pinfunction "PA0/GPIO_EM4WU0/I2C0_SDA#0/LEU0_RX#4/PRS_CH0/TIM0_CC0#0,1,4_1") (pintype "bidirectional"))
    )
    (net (code "104") (name "unconnected-(U1A-PA1{slash}CMU_CLK1#0{slash}I2C0_SCL#0{slash}PRS_CH1{slash}TIM0_CC1#0,1-Pad2)") (class "Default")
      (node (ref "U1") (pin "2") (pinfunction "PA1/CMU_CLK1#0/I2C0_SCL#0/PRS_CH1/TIM0_CC1#0,1_2") (pintype "bidirectional"))
    )
    (net (code "105") (name "unconnected-(U1A-PA2{slash}CMU_CLK0#0{slash}ETM_TD0#3{slash}TIM0_CC2#0,1-Pad3)") (class "Default")
      (node (ref "U1") (pin "3") (pinfunction "PA2/CMU_CLK0#0/ETM_TD0#3/TIM0_CC2#0,1_3") (pintype "bidirectional"))
    )
    (net (code "106") (name "unconnected-(U1A-PA3{slash}ETM_TD1#3{slash}LES_ALTEX2{slash}TIM0_CDTI0#0-Pad4)") (class "Default")
      (node (ref "U1") (pin "4") (pinfunction "PA3/ETM_TD1#3/LES_ALTEX2/TIM0_CDTI0#0_4") (pintype "bidirectional"))
    )
    (net (code "107") (name "unconnected-(U1A-PA4{slash}ETM_TD2#3{slash}LES_ALTEX3{slash}TIM0_CDTI1#0-Pad5)") (class "Default")
      (node (ref "U1") (pin "5") (pinfunction "PA4/ETM_TD2#3/LES_ALTEX3/TIM0_CDTI1#0_5") (pintype "bidirectional"))
    )
    (net (code "108") (name "unconnected-(U1A-PA5{slash}ETM_TD3#3{slash}LES_ALTEX4{slash}LEU1_TX#1{slash}TIM0_CDTI2#0-Pad6)") (class "Default")
      (node (ref "U1") (pin "6") (pinfunction "PA5/ETM_TD3#3/LES_ALTEX4/LEU1_TX#1/TIM0_CDTI2#0_6") (pintype "bidirectional"))
    )
    (net (code "109") (name "unconnected-(U1A-PA6{slash}ETM_TCLK#3{slash}GPIO_EM4WU1{slash}LEU1_RX#1-Pad7)") (class "Default")
      (node (ref "U1") (pin "7") (pinfunction "PA6/ETM_TCLK#3/GPIO_EM4WU1/LEU1_RX#1_7") (pintype "bidirectional"))
    )
    (net (code "110") (name "unconnected-(U1A-PA15{slash}TIM3_CC2-Pad64)") (class "Default")
      (node (ref "U1") (pin "64") (pinfunction "PA15/TIM3_CC2_64") (pintype "bidirectional"))
    )
    (net (code "111") (name "unconnected-(U1C-PC4{slash}ACMP0_CH4{slash}DAC0_P0{slash}OPAMP_P0{slash}I2C1_SDA#0{slash}LES_CH4{slash}LETIM0_OUT0#3{slash}PCNT1_S0IN{slash}TIM0_CDTI2#4{slash}US2_CLK-Pad13)") (class "Default")
      (node (ref "U1") (pin "13") (pinfunction "PC4/ACMP0_CH4/DAC0_P0/OPAMP_P0/I2C1_SDA#0/LES_CH4/LETIM0_OUT0#3/PCNT1_S0IN/TIM0_CDTI2#4/US2_CLK_13") (pintype "bidirectional"))
    )
    (net (code "112") (name "unconnected-(U1C-PC5{slash}ACMP0_CH5{slash}DAC0_N0{slash}OPAMP_N0{slash}I2C1_SCL#0{slash}LES_CH5{slash}LETIM0_OUT1#3{slash}PCNT1_S1IN{slash}US2_CS-Pad14)") (class "Default")
      (node (ref "U1") (pin "14") (pinfunction "PC5/ACMP0_CH5/DAC0_N0/OPAMP_N0/I2C1_SCL#0/LES_CH5/LETIM0_OUT1#3/PCNT1_S1IN/US2_CS_14") (pintype "bidirectional"))
    )
    (net (code "113") (name "unconnected-(U1C-PC8{slash}ACMP1_CH0{slash}LES_CH8{slash}TIM2_CC0#2{slash}US0_CS#2-Pad41)") (class "Default")
      (node (ref "U1") (pin "41") (pinfunction "PC8/ACMP1_CH0/LES_CH8/TIM2_CC0#2/US0_CS#2_41") (pintype "bidirectional"))
    )
    (net (code "114") (name "unconnected-(U1E-PE8{slash}PCNT2_S0IN#1{slash}PRS_CH3#1-Pad56)") (class "Default")
      (node (ref "U1") (pin "56") (pinfunction "PE8/PCNT2_S0IN#1/PRS_CH3#1_56") (pintype "bidirectional"))
    )
    (net (code "115") (name "unconnected-(U1E-PE10{slash}TIM1_CC0#1{slash}US0_TX#0-Pad58)") (class "Default")
      (node (ref "U1") (pin "58") (pinfunction "PE10/TIM1_CC0#1/US0_TX#0_58") (pintype "bidirectional"))
    )
    (net (code "116") (name "unconnected-(U1E-PE11{slash}LES_ALTEX5{slash}TIM1_CC1#1{slash}US0_RX#0-Pad59)") (class "Default")
      (node (ref "U1") (pin "59") (pinfunction "PE11/LES_ALTEX5/TIM1_CC1#1/US0_RX#0_59") (pintype "bidirectional"))
    )
    (net (code "117") (name "unconnected-(U2-ACTIVE-Pad6)") (class "Default")
      (node (ref "U2") (pin "6") (pinfunction "ACTIVE_6") (pintype "bidirectional"))
    )
    (net (code "118") (name "unconnected-(U2-N{slash}C-Pad15)") (class "Default")
      (node (ref "U2") (pin "15") (pinfunction "N/C_15") (pintype "bidirectional"))
    )
    (net (code "119") (name "unconnected-(U2-RXD-Pad10)") (class "Default")
      (node (ref "U2") (pin "10") (pinfunction "RXD_10") (pintype "bidirectional"))
    )
    (net (code "120") (name "unconnected-(U2-TXD-Pad7)") (class "Default")
      (node (ref "U2") (pin "7") (pinfunction "TXD_7") (pintype "bidirectional"))
    )
    (net (code "121") (name "unconnected-(U3-ADC1-Pad16)") (class "Default")
      (node (ref "U3") (pin "16") (pinfunction "ADC1_16") (pintype "bidirectional"))
    )
    (net (code "122") (name "unconnected-(U3-ADC2-Pad15)") (class "Default")
      (node (ref "U3") (pin "15") (pinfunction "ADC2_15") (pintype "bidirectional"))
    )
    (net (code "123") (name "unconnected-(U3-ADC3-Pad13)") (class "Default")
      (node (ref "U3") (pin "13") (pinfunction "ADC3_13") (pintype "bidirectional"))
    )
    (net (code "124") (name "unconnected-(U3-INT2-Pad9)") (class "Default")
      (node (ref "U3") (pin "9") (pinfunction "INT2_9") (pintype "bidirectional"))
    )
    (net (code "125") (name "unconnected-(U3-NC2-Pad2)") (class "Default")
      (node (ref "U3") (pin "2") (pinfunction "NC2_2") (pintype "bidirectional"))
    )
    (net (code "126") (name "unconnected-(U3-NC3-Pad3)") (class "Default")
      (node (ref "U3") (pin "3") (pinfunction "NC3_3") (pintype "bidirectional"))
    )
    (net (code "127") (name "unconnected-(U5-P0-Pad6)") (class "Default")
      (node (ref "U5") (pin "6") (pinfunction "P0_6") (pintype "bidirectional"))
    )
  )
)
